# marbles_v70.net
KiCad netlist of a schematic drawn in EAGLE
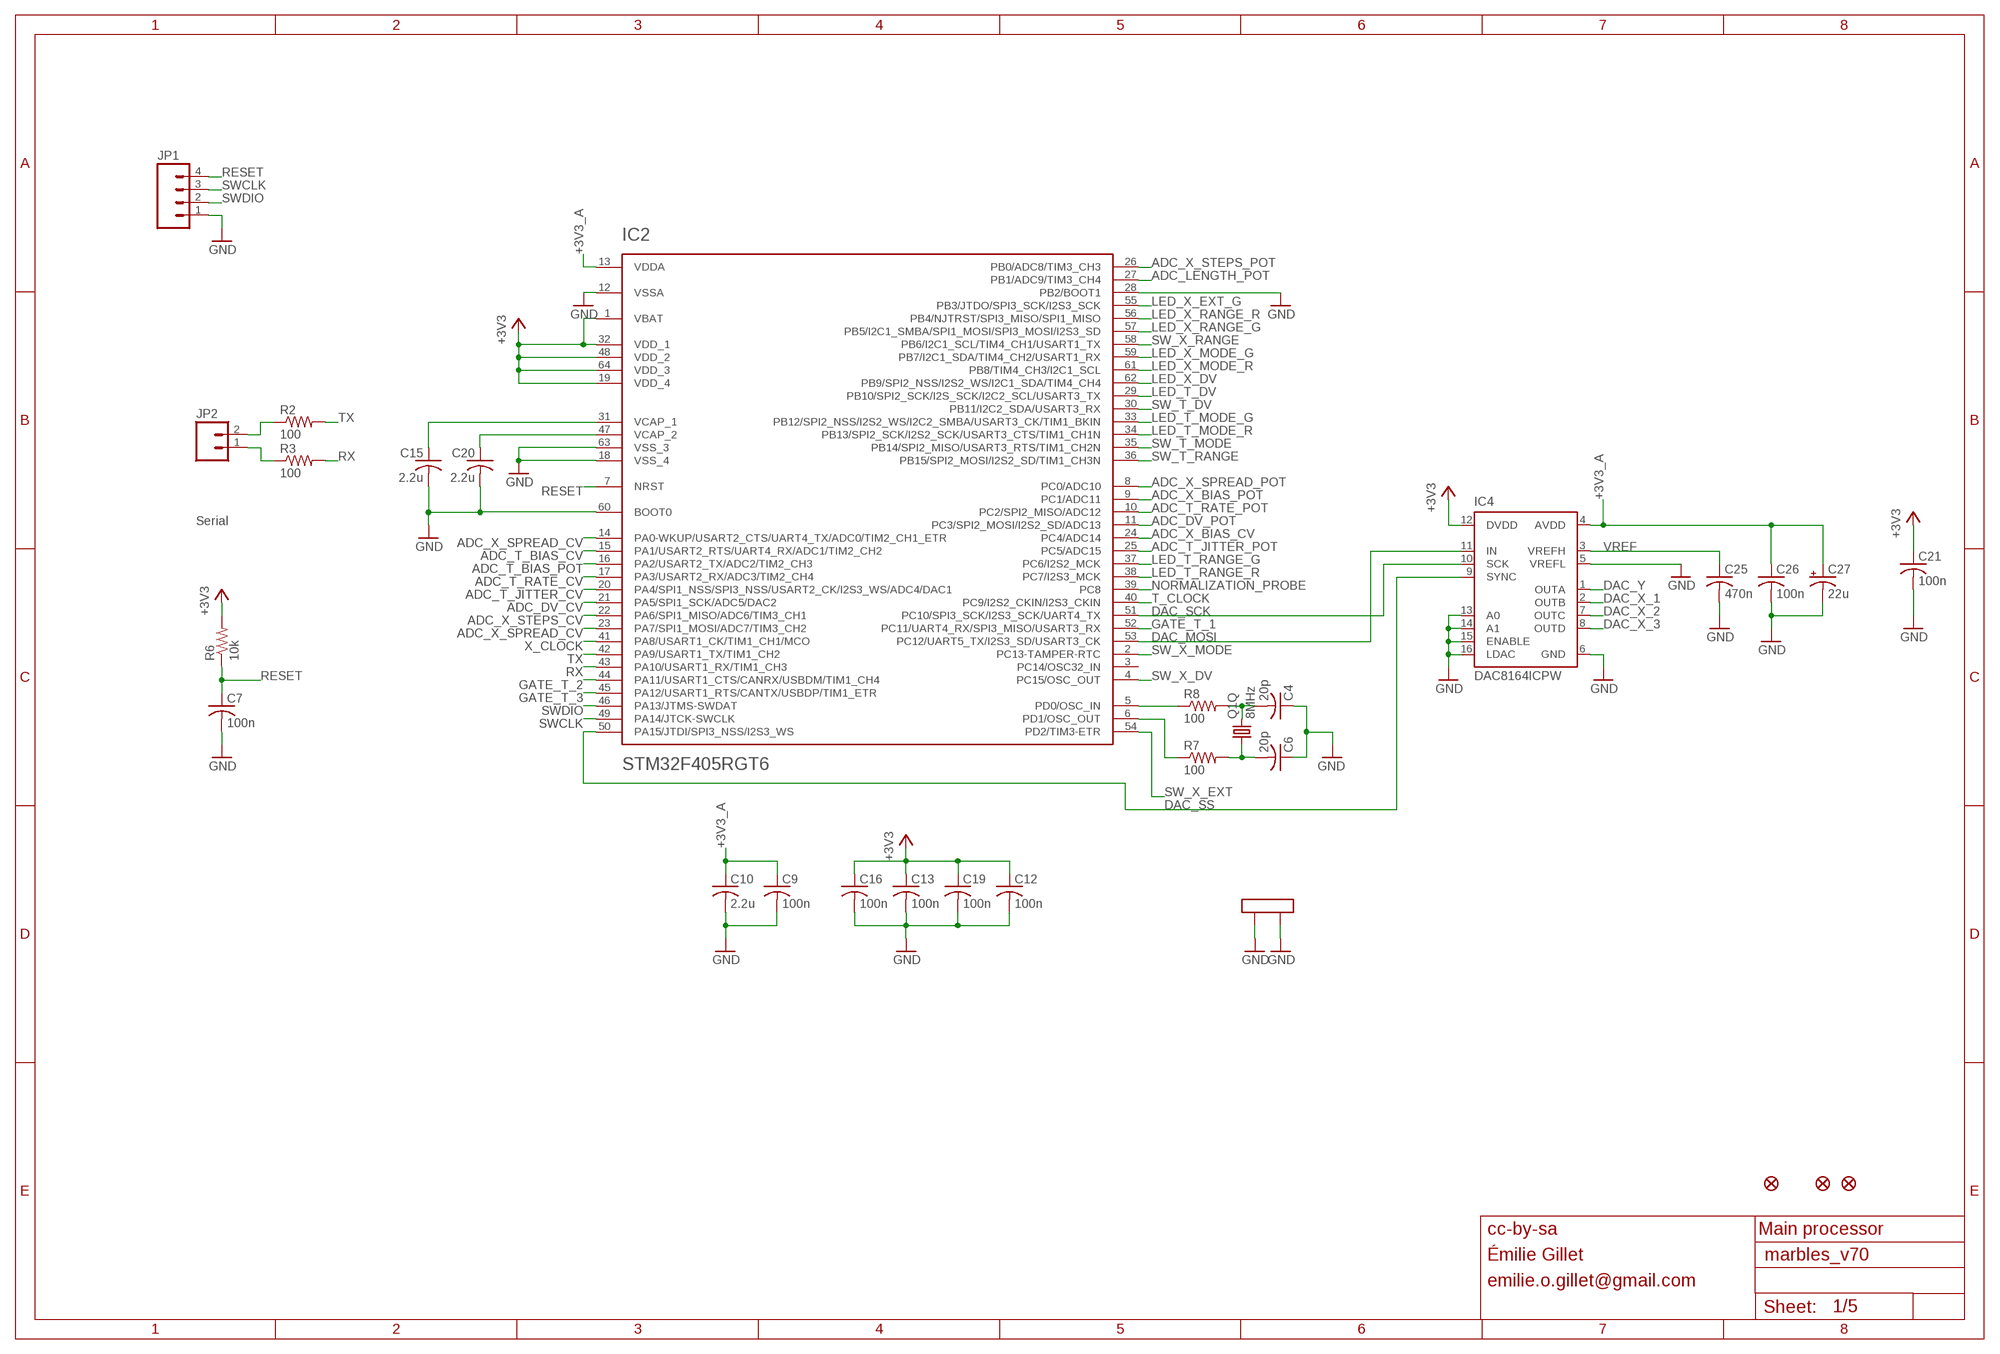
[diagram p0: schematic, sheet 1]
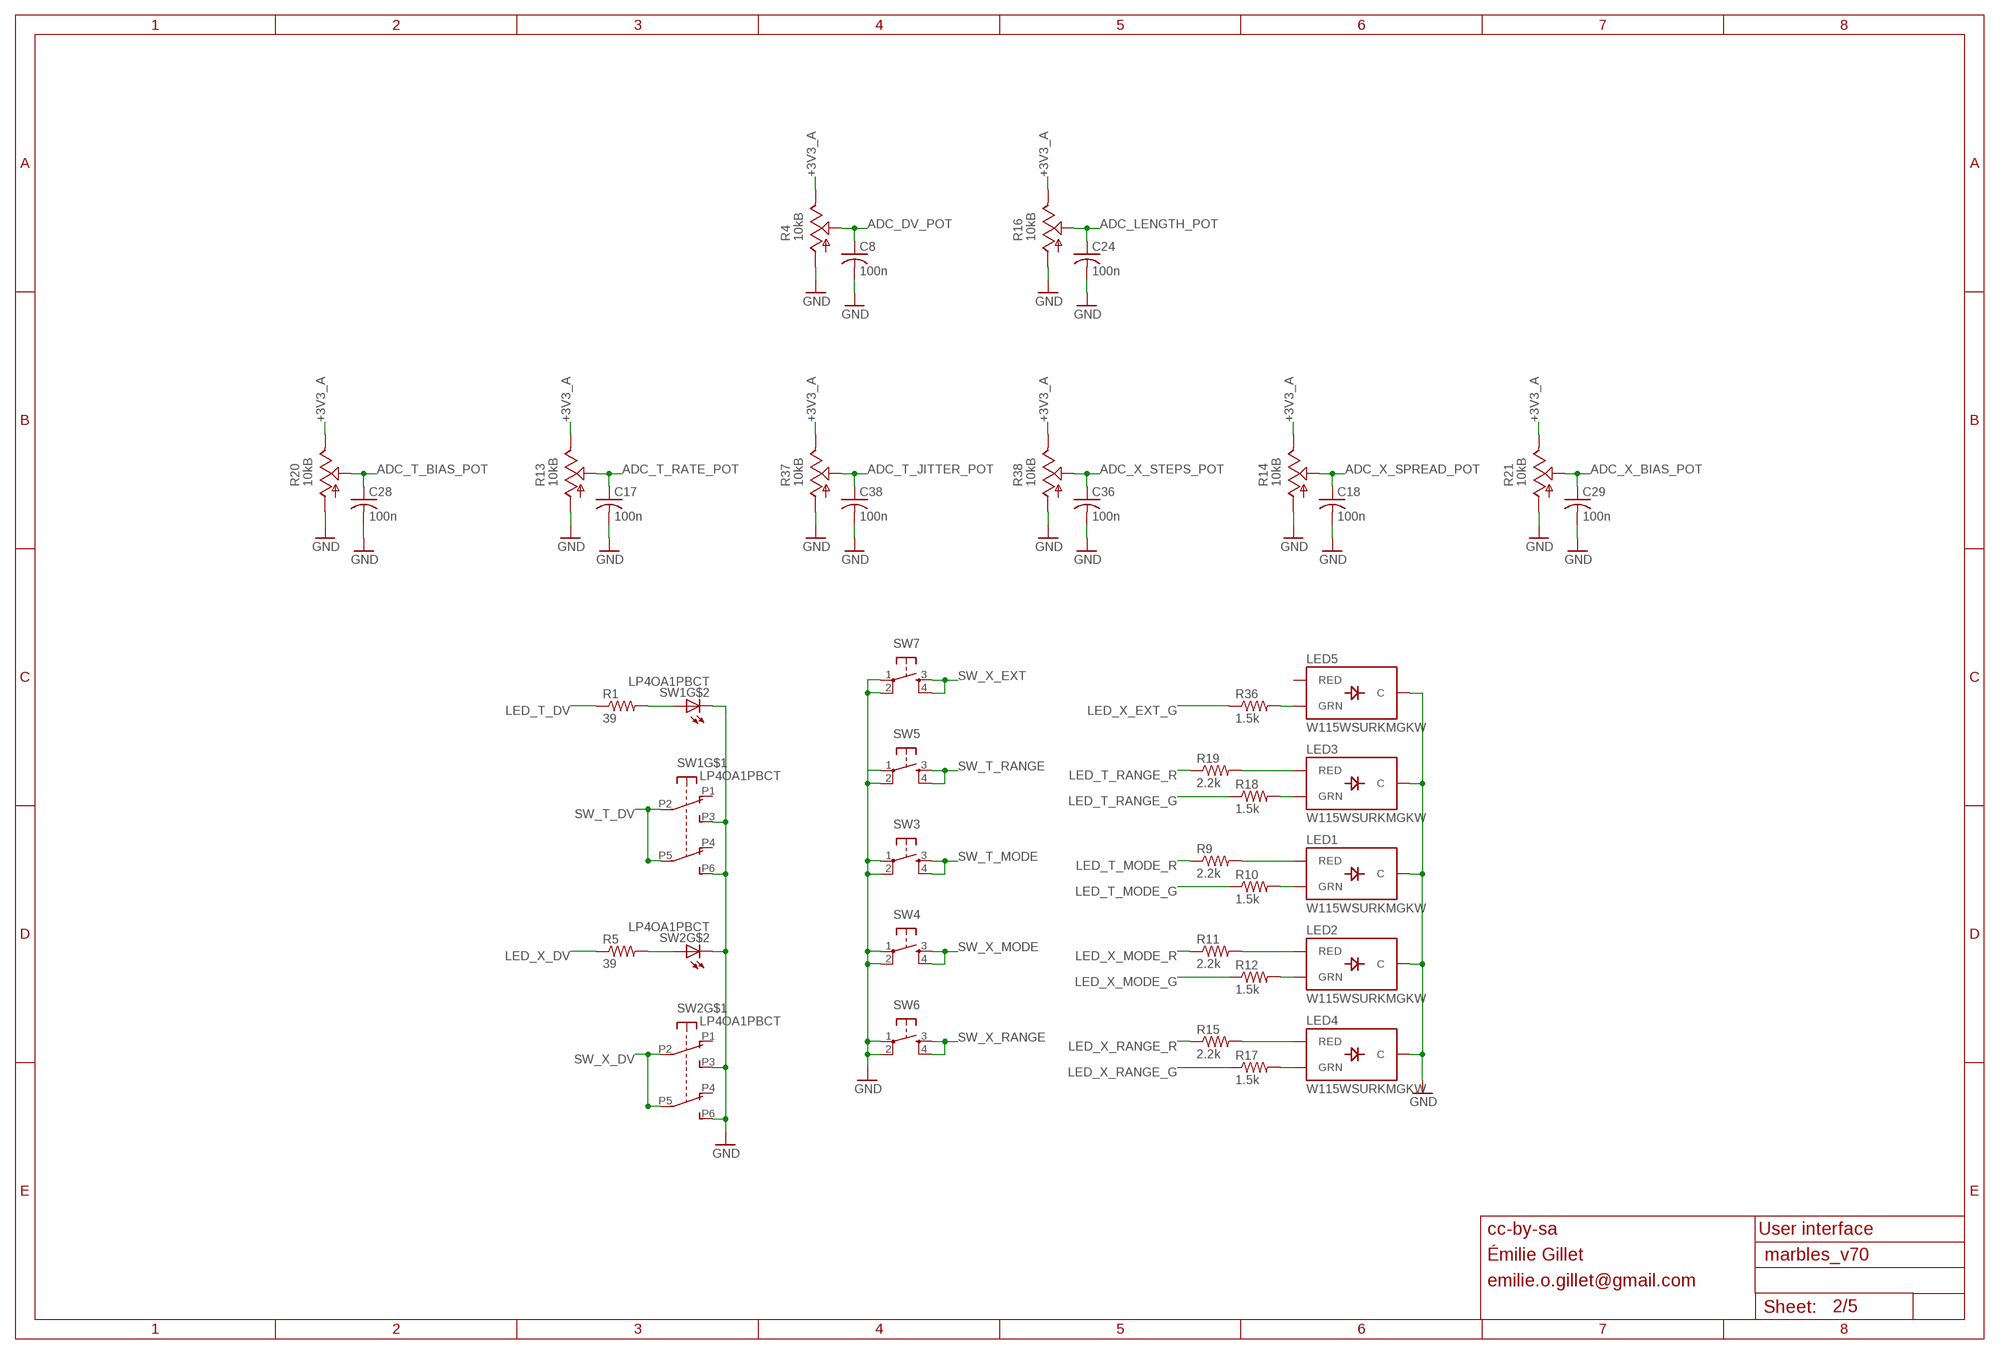
[diagram p1: schematic, sheet 2]
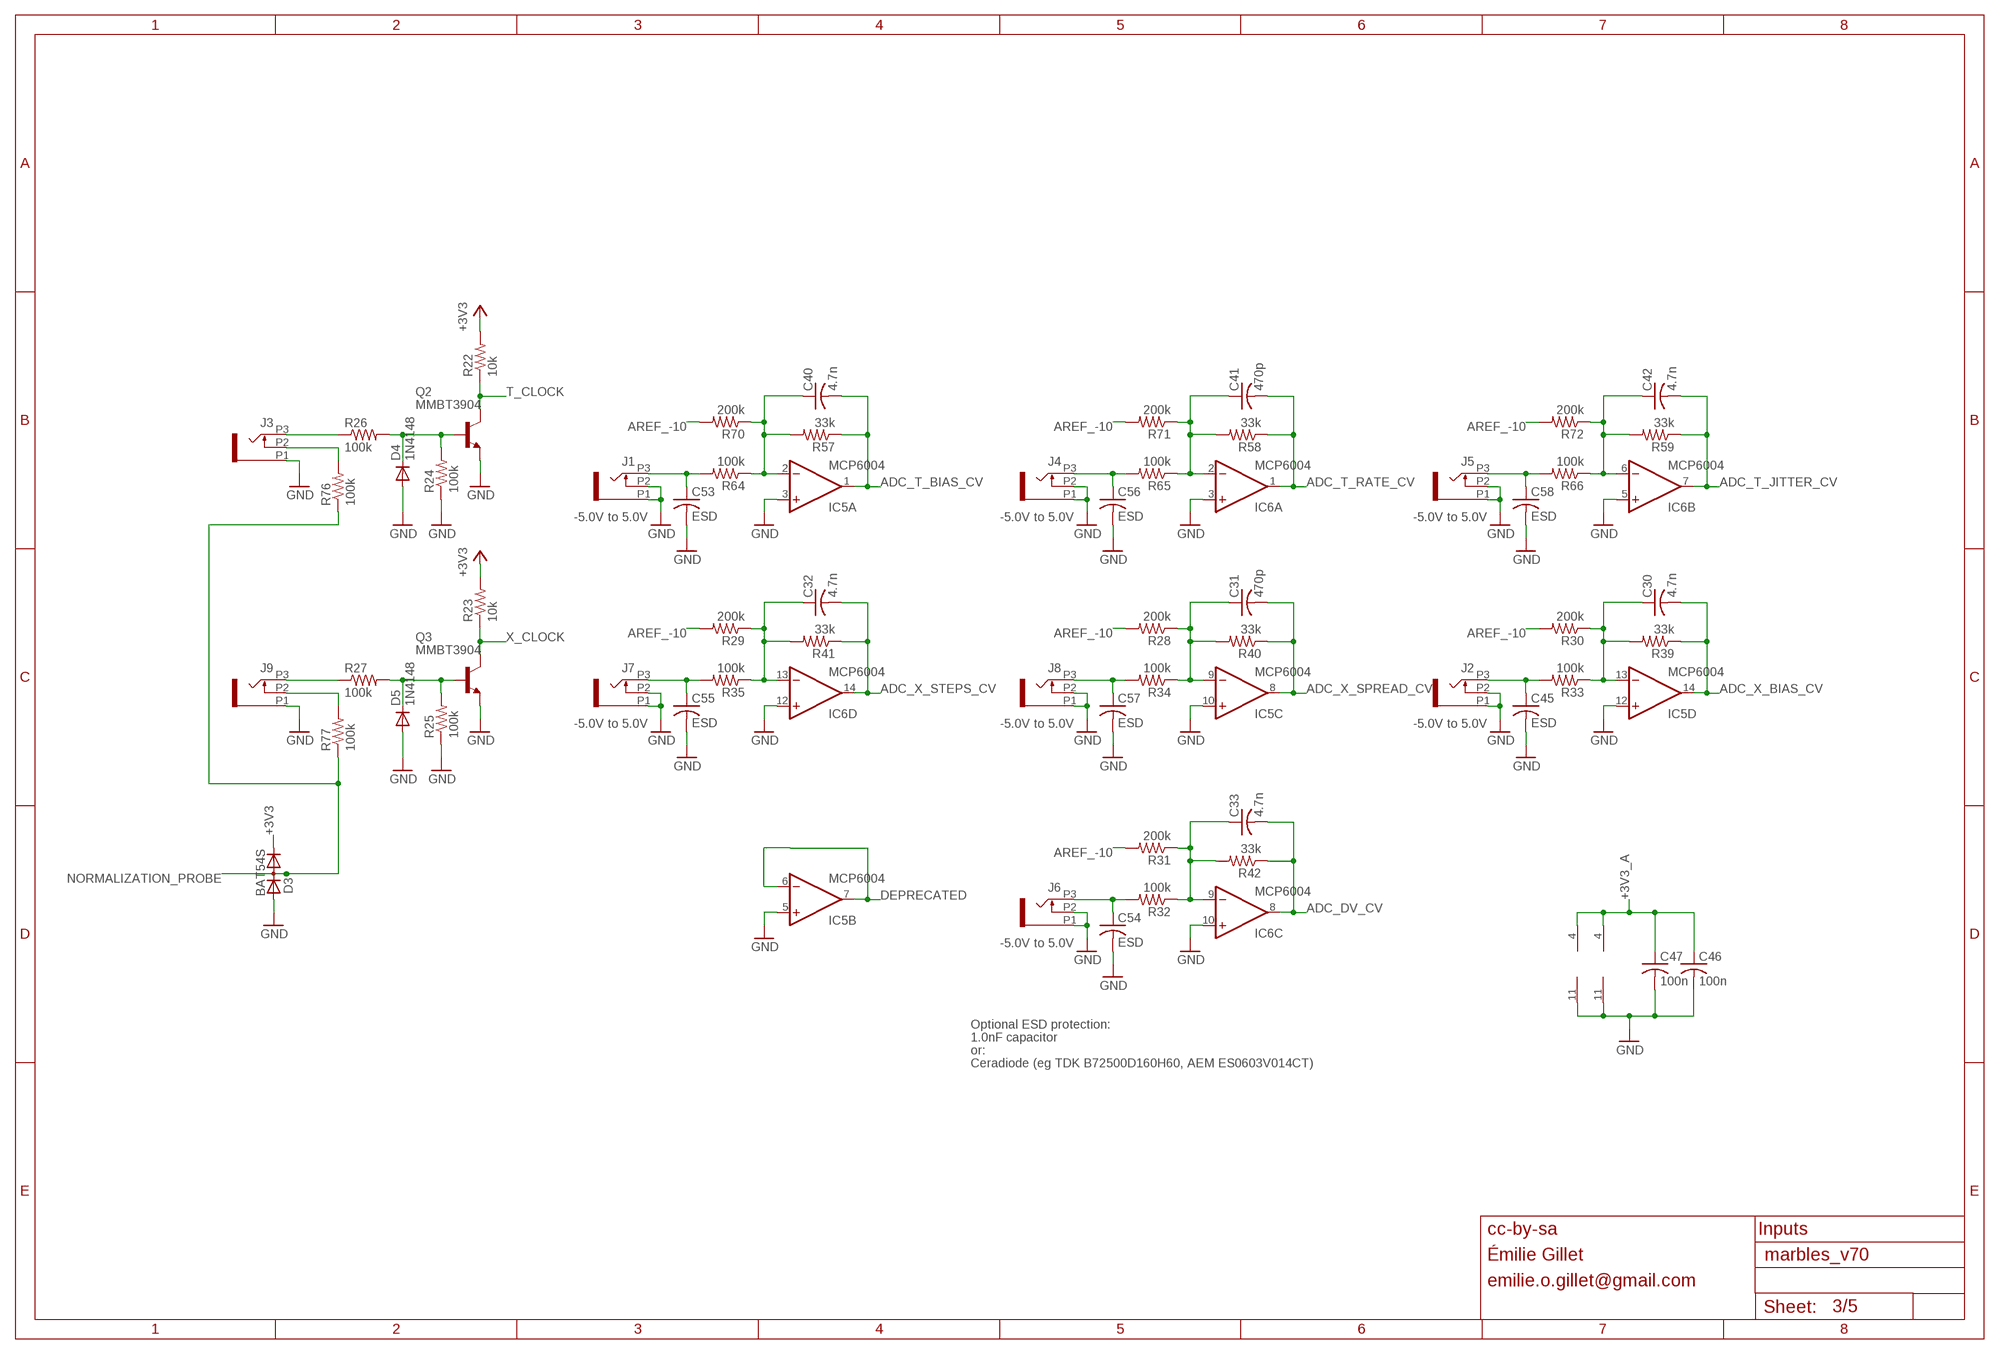
[diagram p2: schematic, sheet 3]
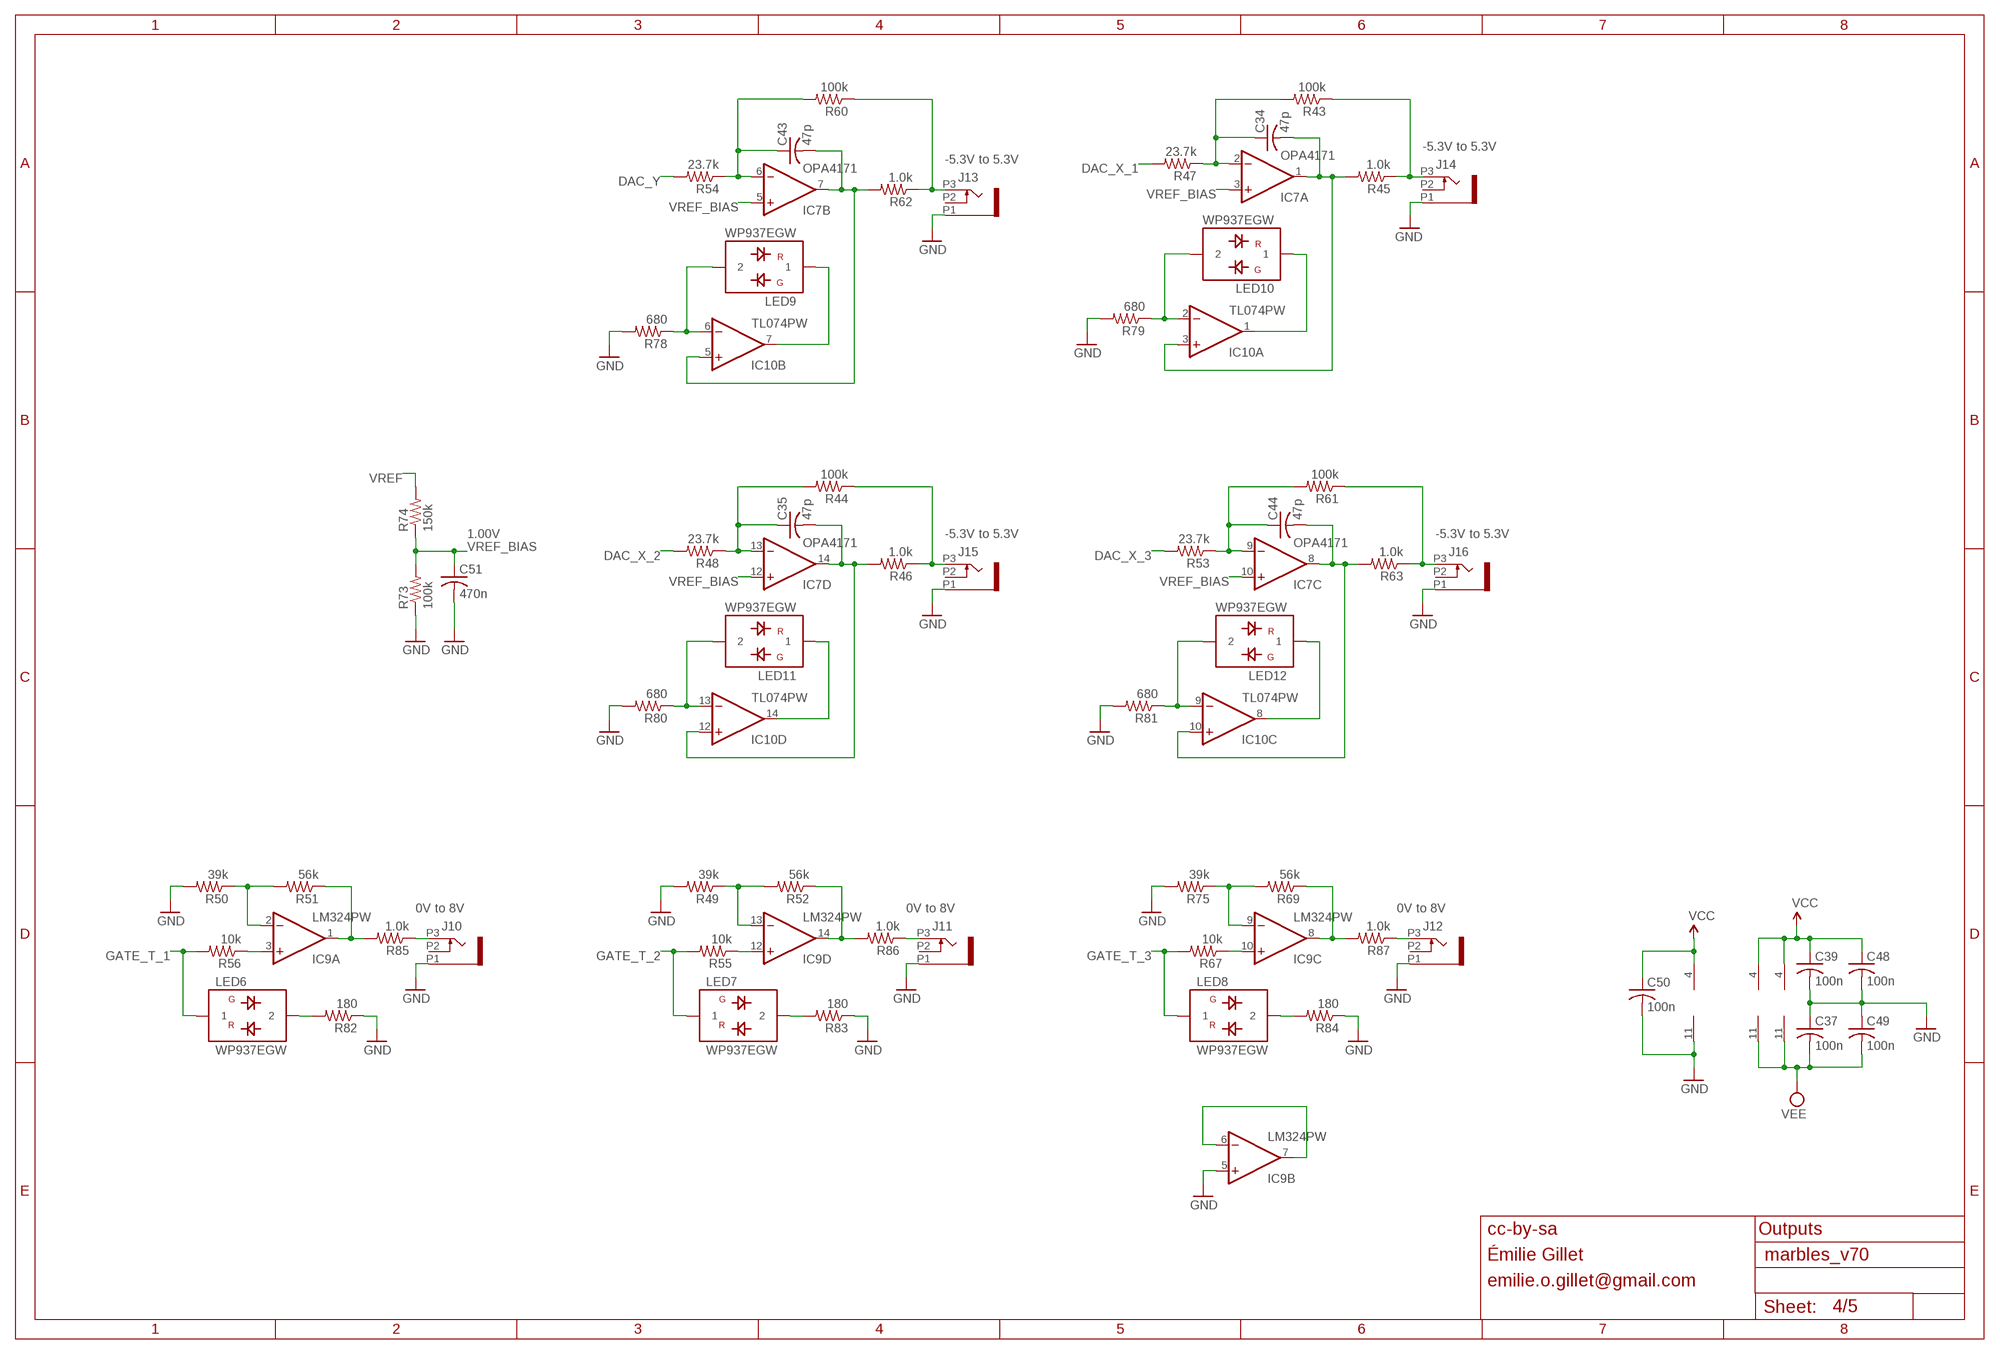
[diagram p3: schematic, sheet 4]
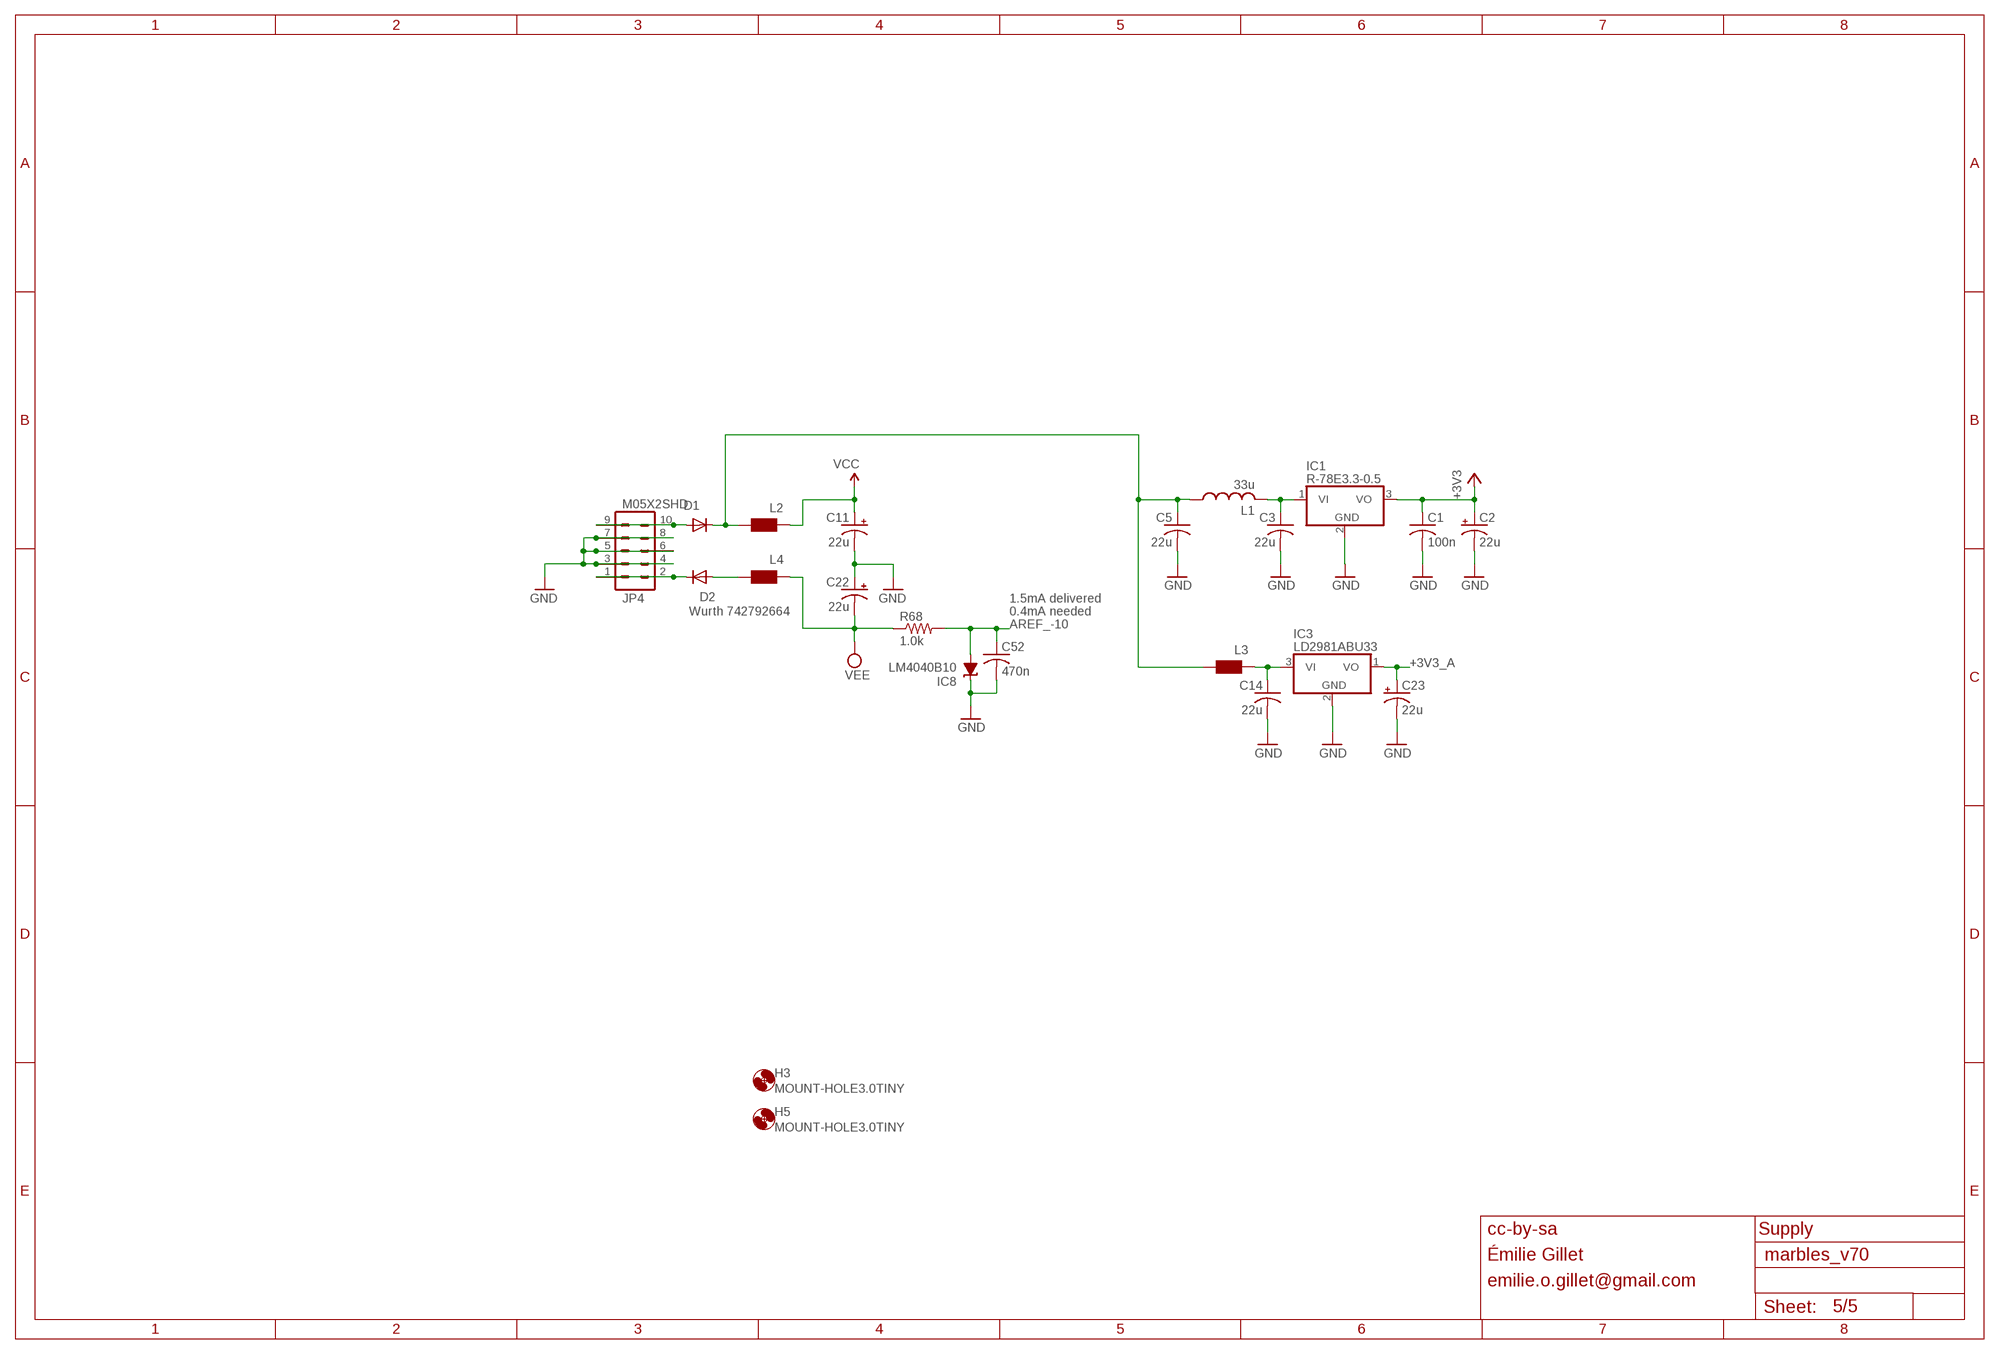
[diagram p4: schematic, sheet 5]

(export (version "E")
  (design (tool "Eeschema 10.0.6"))
  (components
    (comp (ref "C8")
      (value "100n")
      (footprint "eagle-import:C0402")
      (libsource (lib "eagle-import") (part "C-USC0402"))
    )
    (comp (ref "C17")
      (value "100n")
      (footprint "eagle-import:C0402")
      (libsource (lib "eagle-import") (part "C-USC0402"))
    )
    (comp (ref "C18")
      (value "100n")
      (footprint "eagle-import:C0402")
      (libsource (lib "eagle-import") (part "C-USC0402"))
    )
    (comp (ref "C24")
      (value "100n")
      (footprint "eagle-import:C0402")
      (libsource (lib "eagle-import") (part "C-USC0402"))
    )
    (comp (ref "C28")
      (value "100n")
      (footprint "eagle-import:C0402")
      (libsource (lib "eagle-import") (part "C-USC0402"))
    )
    (comp (ref "C29")
      (value "100n")
      (footprint "eagle-import:C0402")
      (libsource (lib "eagle-import") (part "C-USC0402"))
    )
    (comp (ref "C36")
      (value "100n")
      (footprint "eagle-import:C0402")
      (libsource (lib "eagle-import") (part "C-USC0402"))
    )
    (comp (ref "C38")
      (value "100n")
      (footprint "eagle-import:C0402")
      (libsource (lib "eagle-import") (part "C-USC0402"))
    )
    (comp (ref "LED1")
      (value "W115WSURKMGKW")
      (footprint "eagle-import:LED-BICOLOR-THROUGHHOLE-2.54")
      (libsource (lib "eagle-import") (part "LED-BICOLOR-THROUGHHOLE2.54"))
    )
    (comp (ref "LED2")
      (value "W115WSURKMGKW")
      (footprint "eagle-import:LED-BICOLOR-THROUGHHOLE-2.54")
      (libsource (lib "eagle-import") (part "LED-BICOLOR-THROUGHHOLE2.54"))
    )
    (comp (ref "LED3")
      (value "W115WSURKMGKW")
      (footprint "eagle-import:LED-BICOLOR-THROUGHHOLE-2.54")
      (libsource (lib "eagle-import") (part "LED-BICOLOR-THROUGHHOLE2.54"))
    )
    (comp (ref "LED4")
      (value "W115WSURKMGKW")
      (footprint "eagle-import:LED-BICOLOR-THROUGHHOLE-2.54")
      (libsource (lib "eagle-import") (part "LED-BICOLOR-THROUGHHOLE2.54"))
    )
    (comp (ref "LED5")
      (value "W115WSURKMGKW")
      (footprint "eagle-import:LED-BICOLOR-THROUGHHOLE-2.54")
      (libsource (lib "eagle-import") (part "LED-BICOLOR-THROUGHHOLE2.54"))
    )
    (comp (ref "R1")
      (value "39")
      (footprint "eagle-import:R0402")
      (libsource (lib "eagle-import") (part "R-US_R0402"))
    )
    (comp (ref "R4")
      (value "10kB")
      (footprint "eagle-import:ALPS_POT_VERTICAL_PS")
      (libsource (lib "eagle-import") (part "POT_USVERTICAL_PS"))
    )
    (comp (ref "R5")
      (value "39")
      (footprint "eagle-import:R0402")
      (libsource (lib "eagle-import") (part "R-US_R0402"))
    )
    (comp (ref "R9")
      (value "2.2k")
      (footprint "eagle-import:R0402")
      (libsource (lib "eagle-import") (part "R-US_R0402"))
    )
    (comp (ref "R10")
      (value "1.5k")
      (footprint "eagle-import:R0402")
      (libsource (lib "eagle-import") (part "R-US_R0402"))
    )
    (comp (ref "R11")
      (value "2.2k")
      (footprint "eagle-import:R0402")
      (libsource (lib "eagle-import") (part "R-US_R0402"))
    )
    (comp (ref "R12")
      (value "1.5k")
      (footprint "eagle-import:R0402")
      (libsource (lib "eagle-import") (part "R-US_R0402"))
    )
    (comp (ref "R13")
      (value "10kB")
      (footprint "eagle-import:ALPS_POT_VERTICAL_PS")
      (libsource (lib "eagle-import") (part "POT_USVERTICAL_PS"))
    )
    (comp (ref "R14")
      (value "10kB")
      (footprint "eagle-import:ALPS_POT_VERTICAL_PS")
      (libsource (lib "eagle-import") (part "POT_USVERTICAL_PS"))
    )
    (comp (ref "R15")
      (value "2.2k")
      (footprint "eagle-import:R0402")
      (libsource (lib "eagle-import") (part "R-US_R0402"))
    )
    (comp (ref "R16")
      (value "10kB")
      (footprint "eagle-import:ALPS_POT_VERTICAL_PS")
      (libsource (lib "eagle-import") (part "POT_USVERTICAL_PS"))
    )
    (comp (ref "R17")
      (value "1.5k")
      (footprint "eagle-import:R0402")
      (libsource (lib "eagle-import") (part "R-US_R0402"))
    )
    (comp (ref "R18")
      (value "1.5k")
      (footprint "eagle-import:R0402")
      (libsource (lib "eagle-import") (part "R-US_R0402"))
    )
    (comp (ref "R19")
      (value "2.2k")
      (footprint "eagle-import:R0402")
      (libsource (lib "eagle-import") (part "R-US_R0402"))
    )
    (comp (ref "R20")
      (value "10kB")
      (footprint "eagle-import:ALPS_POT_VERTICAL_PS")
      (libsource (lib "eagle-import") (part "POT_USVERTICAL_PS"))
    )
    (comp (ref "R21")
      (value "10kB")
      (footprint "eagle-import:ALPS_POT_VERTICAL_PS")
      (libsource (lib "eagle-import") (part "POT_USVERTICAL_PS"))
    )
    (comp (ref "R36")
      (value "1.5k")
      (footprint "eagle-import:R0402")
      (libsource (lib "eagle-import") (part "R-US_R0402"))
    )
    (comp (ref "R37")
      (value "10kB")
      (footprint "eagle-import:ALPS_POT_VERTICAL_PS")
      (libsource (lib "eagle-import") (part "POT_USVERTICAL_PS"))
    )
    (comp (ref "R38")
      (value "10kB")
      (footprint "eagle-import:ALPS_POT_VERTICAL_PS")
      (libsource (lib "eagle-import") (part "POT_USVERTICAL_PS"))
    )
    (comp (ref "SW1")
      (value "LP4OA1PBCT")
      (footprint "eagle-import:LP4OA1PBCT")
      (libsource (lib "eagle-import") (part "LP4OA1PBCT"))
    )
    (comp (ref "SW2")
      (value "LP4OA1PBCT")
      (footprint "eagle-import:LP4OA1PBCT")
      (libsource (lib "eagle-import") (part "LP4OA1PBCT"))
    )
    (comp (ref "SW3")
      (value "TAC_SWITCHPTH")
      (footprint "eagle-import:TACTILE-PTH")
      (libsource (lib "eagle-import") (part "TAC_SWITCHPTH"))
    )
    (comp (ref "SW4")
      (value "TAC_SWITCHPTH")
      (footprint "eagle-import:TACTILE-PTH")
      (libsource (lib "eagle-import") (part "TAC_SWITCHPTH"))
    )
    (comp (ref "SW5")
      (value "TAC_SWITCHPTH")
      (footprint "eagle-import:TACTILE-PTH")
      (libsource (lib "eagle-import") (part "TAC_SWITCHPTH"))
    )
    (comp (ref "SW6")
      (value "TAC_SWITCHPTH")
      (footprint "eagle-import:TACTILE-PTH")
      (libsource (lib "eagle-import") (part "TAC_SWITCHPTH"))
    )
    (comp (ref "SW7")
      (value "TAC_SWITCHPTH")
      (footprint "eagle-import:TACTILE-PTH")
      (libsource (lib "eagle-import") (part "TAC_SWITCHPTH"))
    )
    (comp (ref "C4")
      (value "20p")
      (footprint "eagle-import:C0402")
      (libsource (lib "eagle-import") (part "C-USC0402"))
    )
    (comp (ref "C6")
      (value "20p")
      (footprint "eagle-import:C0402")
      (libsource (lib "eagle-import") (part "C-USC0402"))
    )
    (comp (ref "C7")
      (value "100n")
      (footprint "eagle-import:C0402")
      (libsource (lib "eagle-import") (part "C-USC0402"))
    )
    (comp (ref "C9")
      (value "100n")
      (footprint "eagle-import:C0402")
      (libsource (lib "eagle-import") (part "C-USC0402"))
    )
    (comp (ref "C10")
      (value "2.2u")
      (footprint "eagle-import:C0805")
      (libsource (lib "eagle-import") (part "C-USC0805"))
    )
    (comp (ref "C12")
      (value "100n")
      (footprint "eagle-import:C0402")
      (libsource (lib "eagle-import") (part "C-USC0402"))
    )
    (comp (ref "C13")
      (value "100n")
      (footprint "eagle-import:C0402")
      (libsource (lib "eagle-import") (part "C-USC0402"))
    )
    (comp (ref "C15")
      (value "2.2u")
      (footprint "eagle-import:C0805")
      (libsource (lib "eagle-import") (part "C-USC0805"))
    )
    (comp (ref "C16")
      (value "100n")
      (footprint "eagle-import:C0402")
      (libsource (lib "eagle-import") (part "C-USC0402"))
    )
    (comp (ref "C19")
      (value "100n")
      (footprint "eagle-import:C0402")
      (libsource (lib "eagle-import") (part "C-USC0402"))
    )
    (comp (ref "C20")
      (value "2.2u")
      (footprint "eagle-import:C0805")
      (libsource (lib "eagle-import") (part "C-USC0805"))
    )
    (comp (ref "C21")
      (value "100n")
      (footprint "eagle-import:C0402")
      (libsource (lib "eagle-import") (part "C-USC0402"))
    )
    (comp (ref "C25")
      (value "470n")
      (footprint "eagle-import:C0402")
      (libsource (lib "eagle-import") (part "C-USC0402"))
    )
    (comp (ref "C26")
      (value "100n")
      (footprint "eagle-import:C0402")
      (libsource (lib "eagle-import") (part "C-USC0402"))
    )
    (comp (ref "C27")
      (value "22u")
      (footprint "eagle-import:PANASONIC_C")
      (libsource (lib "eagle-import") (part "CPOL-USC"))
    )
    (comp (ref "F1")
      (value "FIDUCIAL1X2")
      (footprint "eagle-import:FIDUCIAL-1X2")
      (libsource (lib "eagle-import") (part "FIDUCIAL1X2"))
    )
    (comp (ref "F2")
      (value "FIDUCIAL1X2")
      (footprint "eagle-import:FIDUCIAL-1X2")
      (libsource (lib "eagle-import") (part "FIDUCIAL1X2"))
    )
    (comp (ref "F3")
      (value "FIDUCIAL1X2")
      (footprint "eagle-import:FIDUCIAL-1X2")
      (libsource (lib "eagle-import") (part "FIDUCIAL1X2"))
    )
    (comp (ref "IC2")
      (value "STM32F405RGT6")
      (footprint "eagle-import:TQFP-10X10-64")
      (libsource (lib "eagle-import") (part "STM32F20X"))
    )
    (comp (ref "IC4")
      (value "DAC8164ICPW")
      (footprint "eagle-import:SOP65P640X110-16N")
      (libsource (lib "eagle-import") (part "DAC8564"))
    )
    (comp (ref "JP1")
      (value "M04PTH")
      (footprint "eagle-import:1X04")
      (libsource (lib "eagle-import") (part "M04PTH"))
    )
    (comp (ref "JP2")
      (value "M02PTH")
      (footprint "eagle-import:1X02")
      (libsource (lib "eagle-import") (part "M02PTH"))
    )
    (comp (ref "Q1")
      (value "8MHz")
      (footprint "eagle-import:CTS406")
      (libsource (lib "eagle-import") (part "CRYSTAL"))
    )
    (comp (ref "R2")
      (value "100")
      (footprint "eagle-import:R0402")
      (libsource (lib "eagle-import") (part "R-US_R0402"))
    )
    (comp (ref "R3")
      (value "100")
      (footprint "eagle-import:R0402")
      (libsource (lib "eagle-import") (part "R-US_R0402"))
    )
    (comp (ref "R6")
      (value "10k")
      (footprint "eagle-import:R0402")
      (libsource (lib "eagle-import") (part "R-US_R0402"))
    )
    (comp (ref "R7")
      (value "100")
      (footprint "eagle-import:R0402")
      (libsource (lib "eagle-import") (part "R-US_R0402"))
    )
    (comp (ref "R8")
      (value "100")
      (footprint "eagle-import:R0402")
      (libsource (lib "eagle-import") (part "R-US_R0402"))
    )
    (comp (ref "C1")
      (value "100n")
      (footprint "eagle-import:C0402")
      (libsource (lib "eagle-import") (part "C-USC0402"))
    )
    (comp (ref "C2")
      (value "22u")
      (footprint "eagle-import:PANASONIC_C")
      (libsource (lib "eagle-import") (part "CPOL-USC"))
    )
    (comp (ref "C3")
      (value "22u")
      (footprint "eagle-import:C1206")
      (libsource (lib "eagle-import") (part "C-USC1206"))
    )
    (comp (ref "C5")
      (value "22u")
      (footprint "eagle-import:C1206")
      (libsource (lib "eagle-import") (part "C-USC1206"))
    )
    (comp (ref "C11")
      (value "22u")
      (footprint "eagle-import:PANASONIC_C")
      (libsource (lib "eagle-import") (part "CPOL-USC"))
    )
    (comp (ref "C14")
      (value "22u")
      (footprint "eagle-import:C1206")
      (libsource (lib "eagle-import") (part "C-USC1206"))
    )
    (comp (ref "C22")
      (value "22u")
      (footprint "eagle-import:PANASONIC_C")
      (libsource (lib "eagle-import") (part "CPOL-USC"))
    )
    (comp (ref "C23")
      (value "22u")
      (footprint "eagle-import:PANASONIC_C")
      (libsource (lib "eagle-import") (part "CPOL-USC"))
    )
    (comp (ref "C52")
      (value "470n")
      (footprint "eagle-import:C0402")
      (libsource (lib "eagle-import") (part "C-USC0402"))
    )
    (comp (ref "D1")
      (value "1N5819HW")
      (footprint "eagle-import:SOD123")
      (libsource (lib "eagle-import") (part "DIODE-SOD123"))
    )
    (comp (ref "D2")
      (value "1N5819HW")
      (footprint "eagle-import:SOD123")
      (libsource (lib "eagle-import") (part "DIODE-SOD123"))
    )
    (comp (ref "H3")
      (value "MOUNT-HOLE3.0TINY")
      (footprint "eagle-import:3,0TINY")
      (libsource (lib "eagle-import") (part "MOUNT-HOLE3.0TINY"))
    )
    (comp (ref "H5")
      (value "MOUNT-HOLE3.0TINY")
      (footprint "eagle-import:3,0TINY")
      (libsource (lib "eagle-import") (part "MOUNT-HOLE3.0TINY"))
    )
    (comp (ref "IC1")
      (value "R-78E3.3-0.5")
      (footprint "eagle-import:WE78")
      (libsource (lib "eagle-import") (part "WE173950378"))
    )
    (comp (ref "IC3")
      (value "LD2981ABU33")
      (footprint "eagle-import:SOT89")
      (libsource (lib "eagle-import") (part "LD2981ABU"))
    )
    (comp (ref "IC8")
      (value "LM4040B10")
      (footprint "eagle-import:DBZ_R-PDSO-G3")
      (libsource (lib "eagle-import") (part "LM4041DBZB12"))
    )
    (comp (ref "JP4")
      (value "M05X2SHD")
      (footprint "eagle-import:2X5-SHROUDED")
      (libsource (lib "eagle-import") (part "M05X2SHD"))
    )
    (comp (ref "L1")
      (value "33u")
      (footprint "eagle-import:L2012C")
      (libsource (lib "eagle-import") (part "L-USL2012C"))
    )
    (comp (ref "L2")
      (value "WE-CBF_0603")
      (footprint "eagle-import:0603")
      (libsource (lib "eagle-import") (part "WE-CBF_0603"))
    )
    (comp (ref "L3")
      (value "WE-CBF_0603")
      (footprint "eagle-import:0603")
      (libsource (lib "eagle-import") (part "WE-CBF_0603"))
    )
    (comp (ref "L4")
      (value "WE-CBF_0603")
      (footprint "eagle-import:0603")
      (libsource (lib "eagle-import") (part "WE-CBF_0603"))
    )
    (comp (ref "R68")
      (value "1.0k")
      (footprint "eagle-import:R0402")
      (libsource (lib "eagle-import") (part "R-US_R0402"))
    )
    (comp (ref "C30")
      (value "4.7n")
      (footprint "eagle-import:C0402")
      (libsource (lib "eagle-import") (part "C-USC0402"))
    )
    (comp (ref "C31")
      (value "470p")
      (footprint "eagle-import:C0402")
      (libsource (lib "eagle-import") (part "C-USC0402"))
    )
    (comp (ref "C32")
      (value "4.7n")
      (footprint "eagle-import:C0402")
      (libsource (lib "eagle-import") (part "C-USC0402"))
    )
    (comp (ref "C33")
      (value "4.7n")
      (footprint "eagle-import:C0402")
      (libsource (lib "eagle-import") (part "C-USC0402"))
    )
    (comp (ref "C40")
      (value "4.7n")
      (footprint "eagle-import:C0402")
      (libsource (lib "eagle-import") (part "C-USC0402"))
    )
    (comp (ref "C41")
      (value "470p")
      (footprint "eagle-import:C0402")
      (libsource (lib "eagle-import") (part "C-USC0402"))
    )
    (comp (ref "C42")
      (value "4.7n")
      (footprint "eagle-import:C0402")
      (libsource (lib "eagle-import") (part "C-USC0402"))
    )
    (comp (ref "C45")
      (value "ESD")
      (footprint "eagle-import:C0603")
      (libsource (lib "eagle-import") (part "C-USC0603"))
    )
    (comp (ref "C46")
      (value "100n")
      (footprint "eagle-import:C0402")
      (libsource (lib "eagle-import") (part "C-USC0402"))
    )
    (comp (ref "C47")
      (value "100n")
      (footprint "eagle-import:C0402")
      (libsource (lib "eagle-import") (part "C-USC0402"))
    )
    (comp (ref "C53")
      (value "ESD")
      (footprint "eagle-import:C0603")
      (libsource (lib "eagle-import") (part "C-USC0603"))
    )
    (comp (ref "C54")
      (value "ESD")
      (footprint "eagle-import:C0603")
      (libsource (lib "eagle-import") (part "C-USC0603"))
    )
    (comp (ref "C55")
      (value "ESD")
      (footprint "eagle-import:C0603")
      (libsource (lib "eagle-import") (part "C-USC0603"))
    )
    (comp (ref "C56")
      (value "ESD")
      (footprint "eagle-import:C0603")
      (libsource (lib "eagle-import") (part "C-USC0603"))
    )
    (comp (ref "C57")
      (value "ESD")
      (footprint "eagle-import:C0603")
      (libsource (lib "eagle-import") (part "C-USC0603"))
    )
    (comp (ref "C58")
      (value "ESD")
      (footprint "eagle-import:C0603")
      (libsource (lib "eagle-import") (part "C-USC0603"))
    )
    (comp (ref "D3")
      (value "BAT54S")
      (footprint "eagle-import:SOT23")
      (libsource (lib "eagle-import") (part "DIODE_2CACA-SOT23"))
    )
    (comp (ref "D4")
      (value "1N4148")
      (footprint "eagle-import:SOD523")
      (libsource (lib "eagle-import") (part "DIODE-SOD523"))
    )
    (comp (ref "D5")
      (value "1N4148")
      (footprint "eagle-import:SOD523")
      (libsource (lib "eagle-import") (part "DIODE-SOD523"))
    )
    (comp (ref "IC5")
      (value "MCP6004")
      (footprint "eagle-import:TSSOP14_065")
      (libsource (lib "eagle-import") (part "TL074PW"))
    )
    (comp (ref "IC6")
      (value "MCP6004")
      (footprint "eagle-import:TSSOP14_065")
      (libsource (lib "eagle-import") (part "TL074PW"))
    )
    (comp (ref "J1")
      (value "PJ301_THONKICONN6")
      (footprint "eagle-import:WQP_PJ_301M6")
      (libsource (lib "eagle-import") (part "PJ301_THONKICONN6"))
    )
    (comp (ref "J2")
      (value "PJ301_THONKICONN6")
      (footprint "eagle-import:WQP_PJ_301M6")
      (libsource (lib "eagle-import") (part "PJ301_THONKICONN6"))
    )
    (comp (ref "J3")
      (value "PJ301_THONKICONN6")
      (footprint "eagle-import:WQP_PJ_301M6")
      (libsource (lib "eagle-import") (part "PJ301_THONKICONN6"))
    )
    (comp (ref "J4")
      (value "PJ301_THONKICONN6")
      (footprint "eagle-import:WQP_PJ_301M6")
      (libsource (lib "eagle-import") (part "PJ301_THONKICONN6"))
    )
    (comp (ref "J5")
      (value "PJ301_THONKICONN6")
      (footprint "eagle-import:WQP_PJ_301M6")
      (libsource (lib "eagle-import") (part "PJ301_THONKICONN6"))
    )
    (comp (ref "J6")
      (value "PJ301_THONKICONN6")
      (footprint "eagle-import:WQP_PJ_301M6")
      (libsource (lib "eagle-import") (part "PJ301_THONKICONN6"))
    )
    (comp (ref "J7")
      (value "PJ301_THONKICONN6")
      (footprint "eagle-import:WQP_PJ_301M6")
      (libsource (lib "eagle-import") (part "PJ301_THONKICONN6"))
    )
    (comp (ref "J8")
      (value "PJ301_THONKICONN6")
      (footprint "eagle-import:WQP_PJ_301M6")
      (libsource (lib "eagle-import") (part "PJ301_THONKICONN6"))
    )
    (comp (ref "J9")
      (value "PJ301_THONKICONN6")
      (footprint "eagle-import:WQP_PJ_301M6")
      (libsource (lib "eagle-import") (part "PJ301_THONKICONN6"))
    )
    (comp (ref "Q2")
      (value "MMBT3904")
      (footprint "eagle-import:SOT23-BEC")
      (libsource (lib "eagle-import") (part "-NPN-SOT23-BECMMBT3904LT1"))
    )
    (comp (ref "Q3")
      (value "MMBT3904")
      (footprint "eagle-import:SOT23-BEC")
      (libsource (lib "eagle-import") (part "-NPN-SOT23-BECMMBT3904LT1"))
    )
    (comp (ref "R22")
      (value "10k")
      (footprint "eagle-import:R0402")
      (libsource (lib "eagle-import") (part "R-US_R0402"))
    )
    (comp (ref "R23")
      (value "10k")
      (footprint "eagle-import:R0402")
      (libsource (lib "eagle-import") (part "R-US_R0402"))
    )
    (comp (ref "R24")
      (value "100k")
      (footprint "eagle-import:R0402")
      (libsource (lib "eagle-import") (part "R-US_R0402"))
    )
    (comp (ref "R25")
      (value "100k")
      (footprint "eagle-import:R0402")
      (libsource (lib "eagle-import") (part "R-US_R0402"))
    )
    (comp (ref "R26")
      (value "100k")
      (footprint "eagle-import:R0402")
      (libsource (lib "eagle-import") (part "R-US_R0402"))
    )
    (comp (ref "R27")
      (value "100k")
      (footprint "eagle-import:R0402")
      (libsource (lib "eagle-import") (part "R-US_R0402"))
    )
    (comp (ref "R28")
      (value "200k")
      (footprint "eagle-import:R0402")
      (libsource (lib "eagle-import") (part "R-US_R0402"))
    )
    (comp (ref "R29")
      (value "200k")
      (footprint "eagle-import:R0402")
      (libsource (lib "eagle-import") (part "R-US_R0402"))
    )
    (comp (ref "R30")
      (value "200k")
      (footprint "eagle-import:R0402")
      (libsource (lib "eagle-import") (part "R-US_R0402"))
    )
    (comp (ref "R31")
      (value "200k")
      (footprint "eagle-import:R0402")
      (libsource (lib "eagle-import") (part "R-US_R0402"))
    )
    (comp (ref "R32")
      (value "100k")
      (footprint "eagle-import:R0402")
      (libsource (lib "eagle-import") (part "R-US_R0402"))
    )
    (comp (ref "R33")
      (value "100k")
      (footprint "eagle-import:R0402")
      (libsource (lib "eagle-import") (part "R-US_R0402"))
    )
    (comp (ref "R34")
      (value "100k")
      (footprint "eagle-import:R0402")
      (libsource (lib "eagle-import") (part "R-US_R0402"))
    )
    (comp (ref "R35")
      (value "100k")
      (footprint "eagle-import:R0402")
      (libsource (lib "eagle-import") (part "R-US_R0402"))
    )
    (comp (ref "R39")
      (value "33k")
      (footprint "eagle-import:R0402")
      (libsource (lib "eagle-import") (part "R-US_R0402"))
    )
    (comp (ref "R40")
      (value "33k")
      (footprint "eagle-import:R0402")
      (libsource (lib "eagle-import") (part "R-US_R0402"))
    )
    (comp (ref "R41")
      (value "33k")
      (footprint "eagle-import:R0402")
      (libsource (lib "eagle-import") (part "R-US_R0402"))
    )
    (comp (ref "R42")
      (value "33k")
      (footprint "eagle-import:R0402")
      (libsource (lib "eagle-import") (part "R-US_R0402"))
    )
    (comp (ref "R57")
      (value "33k")
      (footprint "eagle-import:R0402")
      (libsource (lib "eagle-import") (part "R-US_R0402"))
    )
    (comp (ref "R58")
      (value "33k")
      (footprint "eagle-import:R0402")
      (libsource (lib "eagle-import") (part "R-US_R0402"))
    )
    (comp (ref "R59")
      (value "33k")
      (footprint "eagle-import:R0402")
      (libsource (lib "eagle-import") (part "R-US_R0402"))
    )
    (comp (ref "R64")
      (value "100k")
      (footprint "eagle-import:R0402")
      (libsource (lib "eagle-import") (part "R-US_R0402"))
    )
    (comp (ref "R65")
      (value "100k")
      (footprint "eagle-import:R0402")
      (libsource (lib "eagle-import") (part "R-US_R0402"))
    )
    (comp (ref "R66")
      (value "100k")
      (footprint "eagle-import:R0402")
      (libsource (lib "eagle-import") (part "R-US_R0402"))
    )
    (comp (ref "R70")
      (value "200k")
      (footprint "eagle-import:R0402")
      (libsource (lib "eagle-import") (part "R-US_R0402"))
    )
    (comp (ref "R71")
      (value "200k")
      (footprint "eagle-import:R0402")
      (libsource (lib "eagle-import") (part "R-US_R0402"))
    )
    (comp (ref "R72")
      (value "200k")
      (footprint "eagle-import:R0402")
      (libsource (lib "eagle-import") (part "R-US_R0402"))
    )
    (comp (ref "R76")
      (value "100k")
      (footprint "eagle-import:R0402")
      (libsource (lib "eagle-import") (part "R-US_R0402"))
    )
    (comp (ref "R77")
      (value "100k")
      (footprint "eagle-import:R0402")
      (libsource (lib "eagle-import") (part "R-US_R0402"))
    )
    (comp (ref "C34")
      (value "47p")
      (footprint "eagle-import:C0402")
      (libsource (lib "eagle-import") (part "C-USC0402"))
    )
    (comp (ref "C35")
      (value "47p")
      (footprint "eagle-import:C0402")
      (libsource (lib "eagle-import") (part "C-USC0402"))
    )
    (comp (ref "C37")
      (value "100n")
      (footprint "eagle-import:C0402")
      (libsource (lib "eagle-import") (part "C-USC0402"))
    )
    (comp (ref "C39")
      (value "100n")
      (footprint "eagle-import:C0402")
      (libsource (lib "eagle-import") (part "C-USC0402"))
    )
    (comp (ref "C43")
      (value "47p")
      (footprint "eagle-import:C0402")
      (libsource (lib "eagle-import") (part "C-USC0402"))
    )
    (comp (ref "C44")
      (value "47p")
      (footprint "eagle-import:C0402")
      (libsource (lib "eagle-import") (part "C-USC0402"))
    )
    (comp (ref "C48")
      (value "100n")
      (footprint "eagle-import:C0402")
      (libsource (lib "eagle-import") (part "C-USC0402"))
    )
    (comp (ref "C49")
      (value "100n")
      (footprint "eagle-import:C0402")
      (libsource (lib "eagle-import") (part "C-USC0402"))
    )
    (comp (ref "C50")
      (value "100n")
      (footprint "eagle-import:C0402")
      (libsource (lib "eagle-import") (part "C-USC0402"))
    )
    (comp (ref "C51")
      (value "470n")
      (footprint "eagle-import:C0402")
      (libsource (lib "eagle-import") (part "C-USC0402"))
    )
    (comp (ref "IC7")
      (value "OPA4171")
      (footprint "eagle-import:TSSOP14_065")
      (libsource (lib "eagle-import") (part "TL074PW"))
    )
    (comp (ref "IC9")
      (value "LM324PW")
      (footprint "eagle-import:TSSOP14_065")
      (libsource (lib "eagle-import") (part "TL074PW"))
    )
    (comp (ref "IC10")
      (value "TL074PW")
      (footprint "eagle-import:TSSOP14_065")
      (libsource (lib "eagle-import") (part "TL074PW"))
    )
    (comp (ref "J10")
      (value "PJ301_THONKICONN6")
      (footprint "eagle-import:WQP_PJ_301M6")
      (libsource (lib "eagle-import") (part "PJ301_THONKICONN6"))
    )
    (comp (ref "J11")
      (value "PJ301_THONKICONN6")
      (footprint "eagle-import:WQP_PJ_301M6")
      (libsource (lib "eagle-import") (part "PJ301_THONKICONN6"))
    )
    (comp (ref "J12")
      (value "PJ301_THONKICONN6")
      (footprint "eagle-import:WQP_PJ_301M6")
      (libsource (lib "eagle-import") (part "PJ301_THONKICONN6"))
    )
    (comp (ref "J13")
      (value "PJ301_THONKICONN6")
      (footprint "eagle-import:WQP_PJ_301M6")
      (libsource (lib "eagle-import") (part "PJ301_THONKICONN6"))
    )
    (comp (ref "J14")
      (value "PJ301_THONKICONN6")
      (footprint "eagle-import:WQP_PJ_301M6")
      (libsource (lib "eagle-import") (part "PJ301_THONKICONN6"))
    )
    (comp (ref "J15")
      (value "PJ301_THONKICONN6")
      (footprint "eagle-import:WQP_PJ_301M6")
      (libsource (lib "eagle-import") (part "PJ301_THONKICONN6"))
    )
    (comp (ref "J16")
      (value "PJ301_THONKICONN6")
      (footprint "eagle-import:WQP_PJ_301M6")
      (libsource (lib "eagle-import") (part "PJ301_THONKICONN6"))
    )
    (comp (ref "LED6")
      (value "WP937EGW")
      (footprint "eagle-import:LED3MM")
      (libsource (lib "eagle-import") (part "LED-BICOLOR-SHARED-THROUGHHOLE"))
    )
    (comp (ref "LED7")
      (value "WP937EGW")
      (footprint "eagle-import:LED3MM")
      (libsource (lib "eagle-import") (part "LED-BICOLOR-SHARED-THROUGHHOLE"))
    )
    (comp (ref "LED8")
      (value "WP937EGW")
      (footprint "eagle-import:LED3MM")
      (libsource (lib "eagle-import") (part "LED-BICOLOR-SHARED-THROUGHHOLE"))
    )
    (comp (ref "LED9")
      (value "WP937EGW")
      (footprint "eagle-import:LED3MM")
      (libsource (lib "eagle-import") (part "LED-BICOLOR-SHARED-THROUGHHOLE"))
    )
    (comp (ref "LED10")
      (value "WP937EGW")
      (footprint "eagle-import:LED3MM")
      (libsource (lib "eagle-import") (part "LED-BICOLOR-SHARED-THROUGHHOLE"))
    )
    (comp (ref "LED11")
      (value "WP937EGW")
      (footprint "eagle-import:LED3MM")
      (libsource (lib "eagle-import") (part "LED-BICOLOR-SHARED-THROUGHHOLE"))
    )
    (comp (ref "LED12")
      (value "WP937EGW")
      (footprint "eagle-import:LED3MM")
      (libsource (lib "eagle-import") (part "LED-BICOLOR-SHARED-THROUGHHOLE"))
    )
    (comp (ref "R43")
      (value "100k")
      (footprint "eagle-import:R0402")
      (libsource (lib "eagle-import") (part "R-US_R0402"))
    )
    (comp (ref "R44")
      (value "100k")
      (footprint "eagle-import:R0402")
      (libsource (lib "eagle-import") (part "R-US_R0402"))
    )
    (comp (ref "R45")
      (value "1.0k")
      (footprint "eagle-import:R0603")
      (libsource (lib "eagle-import") (part "R-US_R0603"))
    )
    (comp (ref "R46")
      (value "1.0k")
      (footprint "eagle-import:R0603")
      (libsource (lib "eagle-import") (part "R-US_R0603"))
    )
    (comp (ref "R47")
      (value "23.7k")
      (footprint "eagle-import:R0402")
      (libsource (lib "eagle-import") (part "R-US_R0402"))
    )
    (comp (ref "R48")
      (value "23.7k")
      (footprint "eagle-import:R0402")
      (libsource (lib "eagle-import") (part "R-US_R0402"))
    )
    (comp (ref "R49")
      (value "39k")
      (footprint "eagle-import:R0402")
      (libsource (lib "eagle-import") (part "R-US_R0402"))
    )
    (comp (ref "R50")
      (value "39k")
      (footprint "eagle-import:R0402")
      (libsource (lib "eagle-import") (part "R-US_R0402"))
    )
    (comp (ref "R51")
      (value "56k")
      (footprint "eagle-import:R0402")
      (libsource (lib "eagle-import") (part "R-US_R0402"))
    )
    (comp (ref "R52")
      (value "56k")
      (footprint "eagle-import:R0402")
      (libsource (lib "eagle-import") (part "R-US_R0402"))
    )
    (comp (ref "R53")
      (value "23.7k")
      (footprint "eagle-import:R0402")
      (libsource (lib "eagle-import") (part "R-US_R0402"))
    )
    (comp (ref "R54")
      (value "23.7k")
      (footprint "eagle-import:R0402")
      (libsource (lib "eagle-import") (part "R-US_R0402"))
    )
    (comp (ref "R55")
      (value "10k")
      (footprint "eagle-import:R0402")
      (libsource (lib "eagle-import") (part "R-US_R0402"))
    )
    (comp (ref "R56")
      (value "10k")
      (footprint "eagle-import:R0402")
      (libsource (lib "eagle-import") (part "R-US_R0402"))
    )
    (comp (ref "R60")
      (value "100k")
      (footprint "eagle-import:R0402")
      (libsource (lib "eagle-import") (part "R-US_R0402"))
    )
    (comp (ref "R61")
      (value "100k")
      (footprint "eagle-import:R0402")
      (libsource (lib "eagle-import") (part "R-US_R0402"))
    )
    (comp (ref "R62")
      (value "1.0k")
      (footprint "eagle-import:R0603")
      (libsource (lib "eagle-import") (part "R-US_R0603"))
    )
    (comp (ref "R63")
      (value "1.0k")
      (footprint "eagle-import:R0603")
      (libsource (lib "eagle-import") (part "R-US_R0603"))
    )
    (comp (ref "R67")
      (value "10k")
      (footprint "eagle-import:R0402")
      (libsource (lib "eagle-import") (part "R-US_R0402"))
    )
    (comp (ref "R69")
      (value "56k")
      (footprint "eagle-import:R0402")
      (libsource (lib "eagle-import") (part "R-US_R0402"))
    )
    (comp (ref "R73")
      (value "100k")
      (footprint "eagle-import:R0402")
      (libsource (lib "eagle-import") (part "R-US_R0402"))
    )
    (comp (ref "R74")
      (value "150k")
      (footprint "eagle-import:R0402")
      (libsource (lib "eagle-import") (part "R-US_R0402"))
    )
    (comp (ref "R75")
      (value "39k")
      (footprint "eagle-import:R0402")
      (libsource (lib "eagle-import") (part "R-US_R0402"))
    )
    (comp (ref "R78")
      (value "680")
      (footprint "eagle-import:R0402")
      (libsource (lib "eagle-import") (part "R-US_R0402"))
    )
    (comp (ref "R79")
      (value "680")
      (footprint "eagle-import:R0402")
      (libsource (lib "eagle-import") (part "R-US_R0402"))
    )
    (comp (ref "R80")
      (value "680")
      (footprint "eagle-import:R0402")
      (libsource (lib "eagle-import") (part "R-US_R0402"))
    )
    (comp (ref "R81")
      (value "680")
      (footprint "eagle-import:R0402")
      (libsource (lib "eagle-import") (part "R-US_R0402"))
    )
    (comp (ref "R82")
      (value "180")
      (footprint "eagle-import:R0402")
      (libsource (lib "eagle-import") (part "R-US_R0402"))
    )
    (comp (ref "R83")
      (value "180")
      (footprint "eagle-import:R0402")
      (libsource (lib "eagle-import") (part "R-US_R0402"))
    )
    (comp (ref "R84")
      (value "180")
      (footprint "eagle-import:R0402")
      (libsource (lib "eagle-import") (part "R-US_R0402"))
    )
    (comp (ref "R85")
      (value "1.0k")
      (footprint "eagle-import:R0603")
      (libsource (lib "eagle-import") (part "R-US_R0603"))
    )
    (comp (ref "R86")
      (value "1.0k")
      (footprint "eagle-import:R0603")
      (libsource (lib "eagle-import") (part "R-US_R0603"))
    )
    (comp (ref "R87")
      (value "1.0k")
      (footprint "eagle-import:R0603")
      (libsource (lib "eagle-import") (part "R-US_R0603"))
    )
  )
  (nets
    (net (code "1") (name "+3V3") (class "Default")
      (node (ref "C1") (pin "1") (pinfunction "1_1") (pintype "passive"))
      (node (ref "C12") (pin "1") (pinfunction "1_1") (pintype "passive"))
      (node (ref "C13") (pin "1") (pinfunction "1_1") (pintype "passive"))
      (node (ref "C16") (pin "1") (pinfunction "1_1") (pintype "passive"))
      (node (ref "C19") (pin "1") (pinfunction "1_1") (pintype "passive"))
      (node (ref "C2") (pin "+") (pinfunction "+_+") (pintype "passive"))
      (node (ref "C21") (pin "1") (pinfunction "1_1") (pintype "passive"))
      (node (ref "D3") (pin "2") (pinfunction "C_2") (pintype "passive"))
      (node (ref "IC1") (pin "3") (pinfunction "VO_3") (pintype "passive"))
      (node (ref "IC2") (pin "1") (pinfunction "VBAT_1") (pintype "power_in"))
      (node (ref "IC2") (pin "19") (pinfunction "VDD_4_19") (pintype "power_in"))
      (node (ref "IC2") (pin "32") (pinfunction "VDD_1_32") (pintype "power_in"))
      (node (ref "IC2") (pin "48") (pinfunction "VDD_2_48") (pintype "power_in"))
      (node (ref "IC2") (pin "64") (pinfunction "VDD_3_64") (pintype "power_in"))
      (node (ref "IC4") (pin "12") (pinfunction "DVDD_12") (pintype "power_in"))
      (node (ref "R22") (pin "2") (pinfunction "2_2") (pintype "passive"))
      (node (ref "R23") (pin "2") (pinfunction "2_2") (pintype "passive"))
      (node (ref "R6") (pin "2") (pinfunction "2_2") (pintype "passive"))
    )
    (net (code "2") (name "+3V3_A") (class "Default")
      (node (ref "C10") (pin "1") (pinfunction "1_1") (pintype "passive"))
      (node (ref "C23") (pin "+") (pinfunction "+_+") (pintype "passive"))
      (node (ref "C26") (pin "1") (pinfunction "1_1") (pintype "passive"))
      (node (ref "C27") (pin "+") (pinfunction "+_+") (pintype "passive"))
      (node (ref "C46") (pin "1") (pinfunction "1_1") (pintype "passive"))
      (node (ref "C47") (pin "1") (pinfunction "1_1") (pintype "passive"))
      (node (ref "C9") (pin "1") (pinfunction "1_1") (pintype "passive"))
      (node (ref "IC2") (pin "13") (pinfunction "VDDA_13") (pintype "power_in"))
      (node (ref "IC3") (pin "1") (pinfunction "VO_1") (pintype "passive"))
      (node (ref "IC4") (pin "4") (pinfunction "AVDD_4") (pintype "power_in"))
      (node (ref "IC5") (pin "4") (pinfunction "V+_4") (pintype "power_in"))
      (node (ref "IC6") (pin "4") (pinfunction "V+_4") (pintype "power_in"))
      (node (ref "R13") (pin "P$1") (pinfunction "E_P$1") (pintype "passive"))
      (node (ref "R14") (pin "P$1") (pinfunction "E_P$1") (pintype "passive"))
      (node (ref "R16") (pin "P$1") (pinfunction "E_P$1") (pintype "passive"))
      (node (ref "R20") (pin "P$1") (pinfunction "E_P$1") (pintype "passive"))
      (node (ref "R21") (pin "P$1") (pinfunction "E_P$1") (pintype "passive"))
      (node (ref "R37") (pin "P$1") (pinfunction "E_P$1") (pintype "passive"))
      (node (ref "R38") (pin "P$1") (pinfunction "E_P$1") (pintype "passive"))
      (node (ref "R4") (pin "P$1") (pinfunction "E_P$1") (pintype "passive"))
    )
    (net (code "3") (name "ADC_DV_CV") (class "Default")
      (node (ref "C33") (pin "2") (pinfunction "2_2") (pintype "passive"))
      (node (ref "IC2") (pin "21") (pinfunction "PA5/SPI1_SCK/ADC5/DAC2_21") (pintype "bidirectional"))
      (node (ref "IC6") (pin "8") (pinfunction "OUT_8") (pintype "output"))
      (node (ref "R42") (pin "1") (pinfunction "1_1") (pintype "passive"))
    )
    (net (code "4") (name "ADC_DV_POT") (class "Default")
      (node (ref "C8") (pin "1") (pinfunction "1_1") (pintype "passive"))
      (node (ref "IC2") (pin "11") (pinfunction "PC3/SPI2_MOSI/I2S2_SD/ADC13_11") (pintype "bidirectional"))
      (node (ref "R4") (pin "P$2") (pinfunction "S_P$2") (pintype "passive"))
    )
    (net (code "5") (name "ADC_LENGTH_POT") (class "Default")
      (node (ref "C24") (pin "1") (pinfunction "1_1") (pintype "passive"))
      (node (ref "IC2") (pin "27") (pinfunction "PB1/ADC9/TIM3_CH4_27") (pintype "bidirectional"))
      (node (ref "R16") (pin "P$2") (pinfunction "S_P$2") (pintype "passive"))
    )
    (net (code "6") (name "ADC_T_BIAS_CV") (class "Default")
      (node (ref "C40") (pin "2") (pinfunction "2_2") (pintype "passive"))
      (node (ref "IC2") (pin "15") (pinfunction "PA1/USART2_RTS/UART4_RX/ADC1/TIM2_CH2_15") (pintype "bidirectional"))
      (node (ref "IC5") (pin "1") (pinfunction "OUT_1") (pintype "output"))
      (node (ref "R57") (pin "1") (pinfunction "1_1") (pintype "passive"))
    )
    (net (code "7") (name "ADC_T_BIAS_POT") (class "Default")
      (node (ref "C28") (pin "1") (pinfunction "1_1") (pintype "passive"))
      (node (ref "IC2") (pin "16") (pinfunction "PA2/USART2_TX/ADC2/TIM2_CH3_16") (pintype "bidirectional"))
      (node (ref "R20") (pin "P$2") (pinfunction "S_P$2") (pintype "passive"))
    )
    (net (code "8") (name "ADC_T_JITTER_CV") (class "Default")
      (node (ref "C42") (pin "2") (pinfunction "2_2") (pintype "passive"))
      (node (ref "IC2") (pin "20") (pinfunction "PA4/SPI1_NSS/SPI3_NSS/USART2_CK/I2S3_WS/ADC4/DAC1_20") (pintype "bidirectional"))
      (node (ref "IC6") (pin "7") (pinfunction "OUT_7") (pintype "output"))
      (node (ref "R59") (pin "1") (pinfunction "1_1") (pintype "passive"))
    )
    (net (code "9") (name "ADC_T_JITTER_POT") (class "Default")
      (node (ref "C38") (pin "1") (pinfunction "1_1") (pintype "passive"))
      (node (ref "IC2") (pin "25") (pinfunction "PC5/ADC15_25") (pintype "bidirectional"))
      (node (ref "R37") (pin "P$2") (pinfunction "S_P$2") (pintype "passive"))
    )
    (net (code "10") (name "ADC_T_RATE_CV") (class "Default")
      (node (ref "C41") (pin "2") (pinfunction "2_2") (pintype "passive"))
      (node (ref "IC2") (pin "17") (pinfunction "PA3/USART2_RX/ADC3/TIM2_CH4_17") (pintype "bidirectional"))
      (node (ref "IC6") (pin "1") (pinfunction "OUT_1") (pintype "output"))
      (node (ref "R58") (pin "1") (pinfunction "1_1") (pintype "passive"))
    )
    (net (code "11") (name "ADC_T_RATE_POT") (class "Default")
      (node (ref "C17") (pin "1") (pinfunction "1_1") (pintype "passive"))
      (node (ref "IC2") (pin "10") (pinfunction "PC2/SPI2_MISO/ADC12_10") (pintype "bidirectional"))
      (node (ref "R13") (pin "P$2") (pinfunction "S_P$2") (pintype "passive"))
    )
    (net (code "12") (name "ADC_X_BIAS_CV") (class "Default")
      (node (ref "C30") (pin "2") (pinfunction "2_2") (pintype "passive"))
      (node (ref "IC2") (pin "24") (pinfunction "PC4/ADC14_24") (pintype "bidirectional"))
      (node (ref "IC5") (pin "14") (pinfunction "OUT_14") (pintype "output"))
      (node (ref "R39") (pin "1") (pinfunction "1_1") (pintype "passive"))
    )
    (net (code "13") (name "ADC_X_BIAS_POT") (class "Default")
      (node (ref "C29") (pin "1") (pinfunction "1_1") (pintype "passive"))
      (node (ref "IC2") (pin "9") (pinfunction "PC1/ADC11_9") (pintype "bidirectional"))
      (node (ref "R21") (pin "P$2") (pinfunction "S_P$2") (pintype "passive"))
    )
    (net (code "14") (name "ADC_X_SPREAD_CV") (class "Default")
      (node (ref "C31") (pin "2") (pinfunction "2_2") (pintype "passive"))
      (node (ref "IC2") (pin "14") (pinfunction "PA0-WKUP/USART2_CTS/UART4_TX/ADC0/TIM2_CH1_ETR_14") (pintype "bidirectional"))
      (node (ref "IC2") (pin "23") (pinfunction "PA7/SPI1_MOSI/ADC7/TIM3_CH2_23") (pintype "bidirectional"))
      (node (ref "IC5") (pin "8") (pinfunction "OUT_8") (pintype "output"))
      (node (ref "R40") (pin "1") (pinfunction "1_1") (pintype "passive"))
    )
    (net (code "15") (name "ADC_X_SPREAD_POT") (class "Default")
      (node (ref "C18") (pin "1") (pinfunction "1_1") (pintype "passive"))
      (node (ref "IC2") (pin "8") (pinfunction "PC0/ADC10_8") (pintype "bidirectional"))
      (node (ref "R14") (pin "P$2") (pinfunction "S_P$2") (pintype "passive"))
    )
    (net (code "16") (name "ADC_X_STEPS_CV") (class "Default")
      (node (ref "C32") (pin "2") (pinfunction "2_2") (pintype "passive"))
      (node (ref "IC2") (pin "22") (pinfunction "PA6/SPI1_MISO/ADC6/TIM3_CH1_22") (pintype "bidirectional"))
      (node (ref "IC6") (pin "14") (pinfunction "OUT_14") (pintype "output"))
      (node (ref "R41") (pin "1") (pinfunction "1_1") (pintype "passive"))
    )
    (net (code "17") (name "ADC_X_STEPS_POT") (class "Default")
      (node (ref "C36") (pin "1") (pinfunction "1_1") (pintype "passive"))
      (node (ref "IC2") (pin "26") (pinfunction "PB0/ADC8/TIM3_CH3_26") (pintype "bidirectional"))
      (node (ref "R38") (pin "P$2") (pinfunction "S_P$2") (pintype "passive"))
    )
    (net (code "18") (name "AREF_-10") (class "Default")
      (node (ref "C52") (pin "1") (pinfunction "1_1") (pintype "passive"))
      (node (ref "IC8") (pin "2") (pinfunction "A_2") (pintype "passive"))
      (node (ref "R28") (pin "2") (pinfunction "2_2") (pintype "passive"))
      (node (ref "R29") (pin "2") (pinfunction "2_2") (pintype "passive"))
      (node (ref "R30") (pin "2") (pinfunction "2_2") (pintype "passive"))
      (node (ref "R31") (pin "2") (pinfunction "2_2") (pintype "passive"))
      (node (ref "R68") (pin "2") (pinfunction "2_2") (pintype "passive"))
      (node (ref "R70") (pin "2") (pinfunction "2_2") (pintype "passive"))
      (node (ref "R71") (pin "2") (pinfunction "2_2") (pintype "passive"))
      (node (ref "R72") (pin "2") (pinfunction "2_2") (pintype "passive"))
    )
    (net (code "19") (name "DAC_MOSI") (class "Default")
      (node (ref "IC2") (pin "53") (pinfunction "PC12/UART5_TX/I2S3_SD/USART3_CK_53") (pintype "bidirectional"))
      (node (ref "IC4") (pin "11") (pinfunction "IN_11") (pintype "input"))
    )
    (net (code "20") (name "DAC_SCK") (class "Default")
      (node (ref "IC2") (pin "51") (pinfunction "PC10/SPI3_SCK/I2S3_SCK/UART4_TX_51") (pintype "bidirectional"))
      (node (ref "IC4") (pin "10") (pinfunction "SCK_10") (pintype "input"))
    )
    (net (code "21") (name "DAC_SS") (class "Default")
      (node (ref "IC2") (pin "50") (pinfunction "PA15/JTDI/SPI3_NSS/I2S3_WS_50") (pintype "bidirectional"))
      (node (ref "IC4") (pin "9") (pinfunction "SYNC_9") (pintype "input"))
    )
    (net (code "22") (name "DAC_X_1") (class "Default")
      (node (ref "IC4") (pin "2") (pinfunction "OUTB_2") (pintype "output"))
      (node (ref "R47") (pin "2") (pinfunction "2_2") (pintype "passive"))
    )
    (net (code "23") (name "DAC_X_2") (class "Default")
      (node (ref "IC4") (pin "7") (pinfunction "OUTC_7") (pintype "output"))
      (node (ref "R48") (pin "2") (pinfunction "2_2") (pintype "passive"))
    )
    (net (code "24") (name "DAC_X_3") (class "Default")
      (node (ref "IC4") (pin "8") (pinfunction "OUTD_8") (pintype "output"))
      (node (ref "R53") (pin "2") (pinfunction "2_2") (pintype "passive"))
    )
    (net (code "25") (name "DAC_Y") (class "Default")
      (node (ref "IC4") (pin "1") (pinfunction "OUTA_1") (pintype "output"))
      (node (ref "R54") (pin "2") (pinfunction "2_2") (pintype "passive"))
    )
    (net (code "26") (name "DEPRECATED") (class "Default")
      (node (ref "IC5") (pin "6") (pinfunction "-IN_6") (pintype "input"))
      (node (ref "IC5") (pin "7") (pinfunction "OUT_7") (pintype "output"))
    )
    (net (code "27") (name "GATE_T_1") (class "Default")
      (node (ref "IC2") (pin "52") (pinfunction "PC11/UART4_RX/SPI3_MISO/USART3_RX_52") (pintype "bidirectional"))
      (node (ref "LED6") (pin "1") (pinfunction "1_1") (pintype "bidirectional"))
      (node (ref "R56") (pin "2") (pinfunction "2_2") (pintype "passive"))
    )
    (net (code "28") (name "GATE_T_2") (class "Default")
      (node (ref "IC2") (pin "44") (pinfunction "PA11/USART1_CTS/CANRX/USBDM/TIM1_CH4_44") (pintype "bidirectional"))
      (node (ref "LED7") (pin "1") (pinfunction "1_1") (pintype "bidirectional"))
      (node (ref "R55") (pin "2") (pinfunction "2_2") (pintype "passive"))
    )
    (net (code "29") (name "GATE_T_3") (class "Default")
      (node (ref "IC2") (pin "45") (pinfunction "PA12/USART1_RTS/CANTX/USBDP/TIM1_ETR_45") (pintype "bidirectional"))
      (node (ref "LED8") (pin "1") (pinfunction "1_1") (pintype "bidirectional"))
      (node (ref "R67") (pin "2") (pinfunction "2_2") (pintype "passive"))
    )
    (net (code "30") (name "GND") (class "Default")
      (node (ref "C1") (pin "2") (pinfunction "2_2") (pintype "passive"))
      (node (ref "C10") (pin "2") (pinfunction "2_2") (pintype "passive"))
      (node (ref "C11") (pin "-") (pinfunction "-_-") (pintype "passive"))
      (node (ref "C12") (pin "2") (pinfunction "2_2") (pintype "passive"))
      (node (ref "C13") (pin "2") (pinfunction "2_2") (pintype "passive"))
      (node (ref "C14") (pin "2") (pinfunction "2_2") (pintype "passive"))
      (node (ref "C15") (pin "2") (pinfunction "2_2") (pintype "passive"))
      (node (ref "C16") (pin "2") (pinfunction "2_2") (pintype "passive"))
      (node (ref "C17") (pin "2") (pinfunction "2_2") (pintype "passive"))
      (node (ref "C18") (pin "2") (pinfunction "2_2") (pintype "passive"))
      (node (ref "C19") (pin "2") (pinfunction "2_2") (pintype "passive"))
      (node (ref "C2") (pin "-") (pinfunction "-_-") (pintype "passive"))
      (node (ref "C20") (pin "2") (pinfunction "2_2") (pintype "passive"))
      (node (ref "C21") (pin "2") (pinfunction "2_2") (pintype "passive"))
      (node (ref "C22") (pin "+") (pinfunction "+_+") (pintype "passive"))
      (node (ref "C23") (pin "-") (pinfunction "-_-") (pintype "passive"))
      (node (ref "C24") (pin "2") (pinfunction "2_2") (pintype "passive"))
      (node (ref "C25") (pin "2") (pinfunction "2_2") (pintype "passive"))
      (node (ref "C26") (pin "2") (pinfunction "2_2") (pintype "passive"))
      (node (ref "C27") (pin "-") (pinfunction "-_-") (pintype "passive"))
      (node (ref "C28") (pin "2") (pinfunction "2_2") (pintype "passive"))
      (node (ref "C29") (pin "2") (pinfunction "2_2") (pintype "passive"))
      (node (ref "C3") (pin "2") (pinfunction "2_2") (pintype "passive"))
      (node (ref "C36") (pin "2") (pinfunction "2_2") (pintype "passive"))
      (node (ref "C37") (pin "1") (pinfunction "1_1") (pintype "passive"))
      (node (ref "C38") (pin "2") (pinfunction "2_2") (pintype "passive"))
      (node (ref "C39") (pin "2") (pinfunction "2_2") (pintype "passive"))
      (node (ref "C4") (pin "1") (pinfunction "1_1") (pintype "passive"))
      (node (ref "C45") (pin "2") (pinfunction "2_2") (pintype "passive"))
      (node (ref "C46") (pin "2") (pinfunction "2_2") (pintype "passive"))
      (node (ref "C47") (pin "2") (pinfunction "2_2") (pintype "passive"))
      (node (ref "C48") (pin "2") (pinfunction "2_2") (pintype "passive"))
      (node (ref "C49") (pin "1") (pinfunction "1_1") (pintype "passive"))
      (node (ref "C5") (pin "2") (pinfunction "2_2") (pintype "passive"))
      (node (ref "C50") (pin "2") (pinfunction "2_2") (pintype "passive"))
      (node (ref "C51") (pin "2") (pinfunction "2_2") (pintype "passive"))
      (node (ref "C52") (pin "2") (pinfunction "2_2") (pintype "passive"))
      (node (ref "C53") (pin "2") (pinfunction "2_2") (pintype "passive"))
      (node (ref "C54") (pin "2") (pinfunction "2_2") (pintype "passive"))
      (node (ref "C55") (pin "2") (pinfunction "2_2") (pintype "passive"))
      (node (ref "C56") (pin "2") (pinfunction "2_2") (pintype "passive"))
      (node (ref "C57") (pin "2") (pinfunction "2_2") (pintype "passive"))
      (node (ref "C58") (pin "2") (pinfunction "2_2") (pintype "passive"))
      (node (ref "C6") (pin "1") (pinfunction "1_1") (pintype "passive"))
      (node (ref "C7") (pin "2") (pinfunction "2_2") (pintype "passive"))
      (node (ref "C8") (pin "2") (pinfunction "2_2") (pintype "passive"))
      (node (ref "C9") (pin "2") (pinfunction "2_2") (pintype "passive"))
      (node (ref "D3") (pin "1") (pinfunction "A_1") (pintype "passive"))
      (node (ref "D4") (pin "A") (pinfunction "A_A") (pintype "passive"))
      (node (ref "D5") (pin "A") (pinfunction "A_A") (pintype "passive"))
      (node (ref "IC1") (pin "2") (pinfunction "GND_2") (pintype "passive"))
      (node (ref "IC2") (pin "12") (pinfunction "VSSA_12") (pintype "power_in"))
      (node (ref "IC2") (pin "18") (pinfunction "VSS_4_18") (pintype "power_in"))
      (node (ref "IC2") (pin "28") (pinfunction "PB2/BOOT1_28") (pintype "bidirectional"))
      (node (ref "IC2") (pin "60") (pinfunction "BOOT0_60") (pintype "bidirectional"))
      (node (ref "IC2") (pin "63") (pinfunction "VSS_3_63") (pintype "power_in"))
      (node (ref "IC3") (pin "2") (pinfunction "GND_2") (pintype "passive"))
      (node (ref "IC4") (pin "13") (pinfunction "A0_13") (pintype "input"))
      (node (ref "IC4") (pin "14") (pinfunction "A1_14") (pintype "input"))
      (node (ref "IC4") (pin "15") (pinfunction "ENABLE_15") (pintype "input"))
      (node (ref "IC4") (pin "16") (pinfunction "LDAC_16") (pintype "input"))
      (node (ref "IC4") (pin "5") (pinfunction "VREFL_5") (pintype "bidirectional"))
      (node (ref "IC4") (pin "6") (pinfunction "GND_6") (pintype "power_in"))
      (node (ref "IC5") (pin "10") (pinfunction "+IN_10") (pintype "input"))
      (node (ref "IC5") (pin "11") (pinfunction "V-_11") (pintype "power_in"))
      (node (ref "IC5") (pin "12") (pinfunction "+IN_12") (pintype "input"))
      (node (ref "IC5") (pin "3") (pinfunction "+IN_3") (pintype "input"))
      (node (ref "IC5") (pin "5") (pinfunction "+IN_5") (pintype "input"))
      (node (ref "IC6") (pin "10") (pinfunction "+IN_10") (pintype "input"))
      (node (ref "IC6") (pin "11") (pinfunction "V-_11") (pintype "power_in"))
      (node (ref "IC6") (pin "12") (pinfunction "+IN_12") (pintype "input"))
      (node (ref "IC6") (pin "3") (pinfunction "+IN_3") (pintype "input"))
      (node (ref "IC6") (pin "5") (pinfunction "+IN_5") (pintype "input"))
      (node (ref "IC8") (pin "1") (pinfunction "C_1") (pintype "passive"))
      (node (ref "IC9") (pin "11") (pinfunction "V-_11") (pintype "power_in"))
      (node (ref "IC9") (pin "5") (pinfunction "+IN_5") (pintype "input"))
      (node (ref "J1") (pin "P1") (pinfunction "1_P1") (pintype "passive"))
      (node (ref "J1") (pin "P2") (pinfunction "2_P2") (pintype "passive"))
      (node (ref "J10") (pin "P1") (pinfunction "1_P1") (pintype "passive"))
      (node (ref "J11") (pin "P1") (pinfunction "1_P1") (pintype "passive"))
      (node (ref "J12") (pin "P1") (pinfunction "1_P1") (pintype "passive"))
      (node (ref "J13") (pin "P1") (pinfunction "1_P1") (pintype "passive"))
      (node (ref "J14") (pin "P1") (pinfunction "1_P1") (pintype "passive"))
      (node (ref "J15") (pin "P1") (pinfunction "1_P1") (pintype "passive"))
      (node (ref "J16") (pin "P1") (pinfunction "1_P1") (pintype "passive"))
      (node (ref "J2") (pin "P1") (pinfunction "1_P1") (pintype "passive"))
      (node (ref "J2") (pin "P2") (pinfunction "2_P2") (pintype "passive"))
      (node (ref "J3") (pin "P1") (pinfunction "1_P1") (pintype "passive"))
      (node (ref "J4") (pin "P1") (pinfunction "1_P1") (pintype "passive"))
      (node (ref "J4") (pin "P2") (pinfunction "2_P2") (pintype "passive"))
      (node (ref "J5") (pin "P1") (pinfunction "1_P1") (pintype "passive"))
      (node (ref "J5") (pin "P2") (pinfunction "2_P2") (pintype "passive"))
      (node (ref "J6") (pin "P1") (pinfunction "1_P1") (pintype "passive"))
      (node (ref "J6") (pin "P2") (pinfunction "2_P2") (pintype "passive"))
      (node (ref "J7") (pin "P1") (pinfunction "1_P1") (pintype "passive"))
      (node (ref "J7") (pin "P2") (pinfunction "2_P2") (pintype "passive"))
      (node (ref "J8") (pin "P1") (pinfunction "1_P1") (pintype "passive"))
      (node (ref "J8") (pin "P2") (pinfunction "2_P2") (pintype "passive"))
      (node (ref "J9") (pin "P1") (pinfunction "1_P1") (pintype "passive"))
      (node (ref "JP1") (pin "1") (pinfunction "1_1") (pintype "passive"))
      (node (ref "JP4") (pin "3") (pinfunction "3_3") (pintype "passive"))
      (node (ref "JP4") (pin "4") (pinfunction "4_4") (pintype "passive"))
      (node (ref "JP4") (pin "5") (pinfunction "5_5") (pintype "passive"))
      (node (ref "JP4") (pin "6") (pinfunction "6_6") (pintype "passive"))
      (node (ref "JP4") (pin "7") (pinfunction "7_7") (pintype "passive"))
      (node (ref "JP4") (pin "8") (pinfunction "8_8") (pintype "passive"))
      (node (ref "LED1") (pin "2") (pinfunction "C_2") (pintype "bidirectional"))
      (node (ref "LED2") (pin "2") (pinfunction "C_2") (pintype "bidirectional"))
      (node (ref "LED3") (pin "2") (pinfunction "C_2") (pintype "bidirectional"))
      (node (ref "LED4") (pin "2") (pinfunction "C_2") (pintype "bidirectional"))
      (node (ref "LED5") (pin "2") (pinfunction "C_2") (pintype "bidirectional"))
      (node (ref "Q1") (pin "2") (pinfunction "LID1_2") (pintype "power_in"))
      (node (ref "Q1") (pin "4") (pinfunction "LID2_4") (pintype "power_in"))
      (node (ref "Q2") (pin "E") (pinfunction "E_E") (pintype "passive"))
      (node (ref "Q3") (pin "E") (pinfunction "E_E") (pintype "passive"))
      (node (ref "R13") (pin "P$3") (pinfunction "A_P$3") (pintype "passive"))
      (node (ref "R14") (pin "P$3") (pinfunction "A_P$3") (pintype "passive"))
      (node (ref "R16") (pin "P$3") (pinfunction "A_P$3") (pintype "passive"))
      (node (ref "R20") (pin "P$3") (pinfunction "A_P$3") (pintype "passive"))
      (node (ref "R21") (pin "P$3") (pinfunction "A_P$3") (pintype "passive"))
      (node (ref "R24") (pin "1") (pinfunction "1_1") (pintype "passive"))
      (node (ref "R25") (pin "1") (pinfunction "1_1") (pintype "passive"))
      (node (ref "R37") (pin "P$3") (pinfunction "A_P$3") (pintype "passive"))
      (node (ref "R38") (pin "P$3") (pinfunction "A_P$3") (pintype "passive"))
      (node (ref "R4") (pin "P$3") (pinfunction "A_P$3") (pintype "passive"))
      (node (ref "R49") (pin "2") (pinfunction "2_2") (pintype "passive"))
      (node (ref "R50") (pin "2") (pinfunction "2_2") (pintype "passive"))
      (node (ref "R73") (pin "1") (pinfunction "1_1") (pintype "passive"))
      (node (ref "R75") (pin "2") (pinfunction "2_2") (pintype "passive"))
      (node (ref "R78") (pin "2") (pinfunction "2_2") (pintype "passive"))
      (node (ref "R79") (pin "2") (pinfunction "2_2") (pintype "passive"))
      (node (ref "R80") (pin "2") (pinfunction "2_2") (pintype "passive"))
      (node (ref "R81") (pin "2") (pinfunction "2_2") (pintype "passive"))
      (node (ref "R82") (pin "1") (pinfunction "1_1") (pintype "passive"))
      (node (ref "R83") (pin "1") (pinfunction "1_1") (pintype "passive"))
      (node (ref "R84") (pin "1") (pinfunction "1_1") (pintype "passive"))
      (node (ref "SW1") (pin "L2") (pinfunction "L2_L2") (pintype "passive"))
      (node (ref "SW1") (pin "P3") (pinfunction "A3_P3") (pintype "passive"))
      (node (ref "SW1") (pin "P6") (pinfunction "B3_P6") (pintype "passive"))
      (node (ref "SW2") (pin "L2") (pinfunction "L2_L2") (pintype "passive"))
      (node (ref "SW2") (pin "P3") (pinfunction "A3_P3") (pintype "passive"))
      (node (ref "SW2") (pin "P6") (pinfunction "B3_P6") (pintype "passive"))
      (node (ref "SW3") (pin "1") (pinfunction "1_1") (pintype "passive"))
      (node (ref "SW3") (pin "2") (pinfunction "2_2") (pintype "passive"))
      (node (ref "SW4") (pin "1") (pinfunction "1_1") (pintype "passive"))
      (node (ref "SW4") (pin "2") (pinfunction "2_2") (pintype "passive"))
      (node (ref "SW5") (pin "1") (pinfunction "1_1") (pintype "passive"))
      (node (ref "SW5") (pin "2") (pinfunction "2_2") (pintype "passive"))
      (node (ref "SW6") (pin "1") (pinfunction "1_1") (pintype "passive"))
      (node (ref "SW6") (pin "2") (pinfunction "2_2") (pintype "passive"))
      (node (ref "SW7") (pin "1") (pinfunction "1_1") (pintype "passive"))
      (node (ref "SW7") (pin "2") (pinfunction "2_2") (pintype "passive"))
    )
    (net (code "31") (name "LED_T_DV") (class "Default")
      (node (ref "IC2") (pin "29") (pinfunction "PB10/SPI2_SCK/I2S_SCK/I2C2_SCL/USART3_TX_29") (pintype "bidirectional"))
      (node (ref "R1") (pin "1") (pinfunction "1_1") (pintype "passive"))
    )
    (net (code "32") (name "LED_T_MODE_G") (class "Default")
      (node (ref "IC2") (pin "33") (pinfunction "PB12/SPI2_NSS/I2S2_WS/I2C2_SMBA/USART3_CK/TIM1_BKIN_33") (pintype "bidirectional"))
      (node (ref "R10") (pin "1") (pinfunction "1_1") (pintype "passive"))
    )
    (net (code "33") (name "LED_T_MODE_R") (class "Default")
      (node (ref "IC2") (pin "34") (pinfunction "PB13/SPI2_SCK/I2S2_SCK/USART3_CTS/TIM1_CH1N_34") (pintype "bidirectional"))
      (node (ref "R9") (pin "1") (pinfunction "1_1") (pintype "passive"))
    )
    (net (code "34") (name "LED_T_RANGE_G") (class "Default")
      (node (ref "IC2") (pin "37") (pinfunction "PC6/I2S2_MCK_37") (pintype "bidirectional"))
      (node (ref "R18") (pin "1") (pinfunction "1_1") (pintype "passive"))
    )
    (net (code "35") (name "LED_T_RANGE_R") (class "Default")
      (node (ref "IC2") (pin "38") (pinfunction "PC7/I2S3_MCK_38") (pintype "bidirectional"))
      (node (ref "R19") (pin "1") (pinfunction "1_1") (pintype "passive"))
    )
    (net (code "36") (name "LED_X_DV") (class "Default")
      (node (ref "IC2") (pin "62") (pinfunction "PB9/SPI2_NSS/I2S2_WS/I2C1_SDA/TIM4_CH4_62") (pintype "bidirectional"))
      (node (ref "R5") (pin "1") (pinfunction "1_1") (pintype "passive"))
    )
    (net (code "37") (name "LED_X_EXT_G") (class "Default")
      (node (ref "IC2") (pin "55") (pinfunction "PB3/JTDO/SPI3_SCK/I2S3_SCK_55") (pintype "bidirectional"))
      (node (ref "R36") (pin "1") (pinfunction "1_1") (pintype "passive"))
    )
    (net (code "38") (name "LED_X_MODE_G") (class "Default")
      (node (ref "IC2") (pin "59") (pinfunction "PB7/I2C1_SDA/TIM4_CH2/USART1_RX_59") (pintype "bidirectional"))
      (node (ref "R12") (pin "1") (pinfunction "1_1") (pintype "passive"))
    )
    (net (code "39") (name "LED_X_MODE_R") (class "Default")
      (node (ref "IC2") (pin "61") (pinfunction "PB8/TIM4_CH3/I2C1_SCL_61") (pintype "bidirectional"))
      (node (ref "R11") (pin "1") (pinfunction "1_1") (pintype "passive"))
    )
    (net (code "40") (name "LED_X_RANGE_G") (class "Default")
      (node (ref "IC2") (pin "57") (pinfunction "PB5/I2C1_SMBA/SPI1_MOSI/SPI3_MOSI/I2S3_SD_57") (pintype "bidirectional"))
      (node (ref "R17") (pin "1") (pinfunction "1_1") (pintype "passive"))
    )
    (net (code "41") (name "LED_X_RANGE_R") (class "Default")
      (node (ref "IC2") (pin "56") (pinfunction "PB4/NJTRST/SPI3_MISO/SPI1_MISO_56") (pintype "bidirectional"))
      (node (ref "R15") (pin "1") (pinfunction "1_1") (pintype "passive"))
    )
    (net (code "42") (name "NORMALIZATION_PROBE") (class "Default")
      (node (ref "D3") (pin "3") (pinfunction "AC_3") (pintype "passive"))
      (node (ref "IC2") (pin "39") (pinfunction "PC8_39") (pintype "bidirectional"))
      (node (ref "R76") (pin "1") (pinfunction "1_1") (pintype "passive"))
      (node (ref "R77") (pin "1") (pinfunction "1_1") (pintype "passive"))
    )
    (net (code "43") (name "Net-(C5-Pad1)") (class "Default")
      (node (ref "C5") (pin "1") (pinfunction "1_1") (pintype "passive"))
      (node (ref "D1") (pin "C") (pinfunction "C_C") (pintype "passive"))
      (node (ref "L1") (pin "1") (pinfunction "1_1") (pintype "passive"))
      (node (ref "L2") (pin "2") (pinfunction "2_2") (pintype "passive"))
      (node (ref "L3") (pin "2") (pinfunction "2_2") (pintype "passive"))
    )
    (net (code "44") (name "Net-(C6-Pad2)") (class "Default")
      (node (ref "C6") (pin "2") (pinfunction "2_2") (pintype "passive"))
      (node (ref "Q1") (pin "1") (pinfunction "1_1") (pintype "passive"))
      (node (ref "R7") (pin "2") (pinfunction "2_2") (pintype "passive"))
    )
    (net (code "45") (name "Net-(D1-PadA)") (class "Default")
      (node (ref "D1") (pin "A") (pinfunction "A_A") (pintype "passive"))
      (node (ref "JP4") (pin "10") (pinfunction "10_10") (pintype "passive"))
      (node (ref "JP4") (pin "9") (pinfunction "9_9") (pintype "passive"))
    )
    (net (code "46") (name "Net-(D2-PadA)") (class "Default")
      (node (ref "D2") (pin "A") (pinfunction "A_A") (pintype "passive"))
      (node (ref "L4") (pin "2") (pinfunction "2_2") (pintype "passive"))
    )
    (net (code "47") (name "Net-(D2-PadC)") (class "Default")
      (node (ref "D2") (pin "C") (pinfunction "C_C") (pintype "passive"))
      (node (ref "JP4") (pin "1") (pinfunction "1_1") (pintype "passive"))
      (node (ref "JP4") (pin "2") (pinfunction "2_2") (pintype "passive"))
    )
    (net (code "48") (name "Net-(D4-PadC)") (class "Default")
      (node (ref "D4") (pin "C") (pinfunction "C_C") (pintype "passive"))
      (node (ref "Q2") (pin "B") (pinfunction "B_B") (pintype "passive"))
      (node (ref "R24") (pin "2") (pinfunction "2_2") (pintype "passive"))
      (node (ref "R26") (pin "2") (pinfunction "2_2") (pintype "passive"))
    )
    (net (code "49") (name "Net-(D5-PadC)") (class "Default")
      (node (ref "D5") (pin "C") (pinfunction "C_C") (pintype "passive"))
      (node (ref "Q3") (pin "B") (pinfunction "B_B") (pintype "passive"))
      (node (ref "R25") (pin "2") (pinfunction "2_2") (pintype "passive"))
      (node (ref "R27") (pin "2") (pinfunction "2_2") (pintype "passive"))
    )
    (net (code "50") (name "Net-(IC1-VI)") (class "Default")
      (node (ref "C3") (pin "1") (pinfunction "1_1") (pintype "passive"))
      (node (ref "IC1") (pin "1") (pinfunction "VI_1") (pintype "input"))
      (node (ref "L1") (pin "2") (pinfunction "2_2") (pintype "passive"))
    )
    (net (code "51") (name "Net-(IC2-PD0{slash}OSC_IN)") (class "Default")
      (node (ref "IC2") (pin "5") (pinfunction "PD0/OSC_IN_5") (pintype "bidirectional"))
      (node (ref "R8") (pin "1") (pinfunction "1_1") (pintype "passive"))
    )
    (net (code "52") (name "Net-(IC2-PD1{slash}OSC_OUT)") (class "Default")
      (node (ref "IC2") (pin "6") (pinfunction "PD1/OSC_OUT_6") (pintype "bidirectional"))
      (node (ref "R7") (pin "1") (pinfunction "1_1") (pintype "passive"))
    )
    (net (code "53") (name "Net-(IC2-VCAP_1)") (class "Default")
      (node (ref "C15") (pin "1") (pinfunction "1_1") (pintype "passive"))
      (node (ref "IC2") (pin "31") (pinfunction "VCAP_1_31") (pintype "power_in"))
    )
    (net (code "54") (name "Net-(IC2-VCAP_2)") (class "Default")
      (node (ref "C20") (pin "1") (pinfunction "1_1") (pintype "passive"))
      (node (ref "IC2") (pin "47") (pinfunction "VCAP_2_47") (pintype "power_in"))
    )
    (net (code "55") (name "Net-(IC3-VI)") (class "Default")
      (node (ref "C14") (pin "1") (pinfunction "1_1") (pintype "passive"))
      (node (ref "IC3") (pin "3") (pinfunction "VI_3") (pintype "input"))
      (node (ref "L3") (pin "1") (pinfunction "1_1") (pintype "passive"))
    )
    (net (code "56") (name "Net-(IC5A--IN)") (class "Default")
      (node (ref "C40") (pin "1") (pinfunction "1_1") (pintype "passive"))
      (node (ref "IC5") (pin "2") (pinfunction "-IN_2") (pintype "input"))
      (node (ref "R57") (pin "2") (pinfunction "2_2") (pintype "passive"))
      (node (ref "R64") (pin "1") (pinfunction "1_1") (pintype "passive"))
      (node (ref "R70") (pin "1") (pinfunction "1_1") (pintype "passive"))
    )
    (net (code "57") (name "Net-(IC5C--IN)") (class "Default")
      (node (ref "C31") (pin "1") (pinfunction "1_1") (pintype "passive"))
      (node (ref "IC5") (pin "9") (pinfunction "-IN_9") (pintype "input"))
      (node (ref "R28") (pin "1") (pinfunction "1_1") (pintype "passive"))
      (node (ref "R34") (pin "1") (pinfunction "1_1") (pintype "passive"))
      (node (ref "R40") (pin "2") (pinfunction "2_2") (pintype "passive"))
    )
    (net (code "58") (name "Net-(IC5D--IN)") (class "Default")
      (node (ref "C30") (pin "1") (pinfunction "1_1") (pintype "passive"))
      (node (ref "IC5") (pin "13") (pinfunction "-IN_13") (pintype "input"))
      (node (ref "R30") (pin "1") (pinfunction "1_1") (pintype "passive"))
      (node (ref "R33") (pin "1") (pinfunction "1_1") (pintype "passive"))
      (node (ref "R39") (pin "2") (pinfunction "2_2") (pintype "passive"))
    )
    (net (code "59") (name "Net-(IC6A--IN)") (class "Default")
      (node (ref "C41") (pin "1") (pinfunction "1_1") (pintype "passive"))
      (node (ref "IC6") (pin "2") (pinfunction "-IN_2") (pintype "input"))
      (node (ref "R58") (pin "2") (pinfunction "2_2") (pintype "passive"))
      (node (ref "R65") (pin "1") (pinfunction "1_1") (pintype "passive"))
      (node (ref "R71") (pin "1") (pinfunction "1_1") (pintype "passive"))
    )
    (net (code "60") (name "Net-(IC6B--IN)") (class "Default")
      (node (ref "C42") (pin "1") (pinfunction "1_1") (pintype "passive"))
      (node (ref "IC6") (pin "6") (pinfunction "-IN_6") (pintype "input"))
      (node (ref "R59") (pin "2") (pinfunction "2_2") (pintype "passive"))
      (node (ref "R66") (pin "1") (pinfunction "1_1") (pintype "passive"))
      (node (ref "R72") (pin "1") (pinfunction "1_1") (pintype "passive"))
    )
    (net (code "61") (name "Net-(IC6C--IN)") (class "Default")
      (node (ref "C33") (pin "1") (pinfunction "1_1") (pintype "passive"))
      (node (ref "IC6") (pin "9") (pinfunction "-IN_9") (pintype "input"))
      (node (ref "R31") (pin "1") (pinfunction "1_1") (pintype "passive"))
      (node (ref "R32") (pin "1") (pinfunction "1_1") (pintype "passive"))
      (node (ref "R42") (pin "2") (pinfunction "2_2") (pintype "passive"))
    )
    (net (code "62") (name "Net-(IC6D--IN)") (class "Default")
      (node (ref "C32") (pin "1") (pinfunction "1_1") (pintype "passive"))
      (node (ref "IC6") (pin "13") (pinfunction "-IN_13") (pintype "input"))
      (node (ref "R29") (pin "1") (pinfunction "1_1") (pintype "passive"))
      (node (ref "R35") (pin "1") (pinfunction "1_1") (pintype "passive"))
      (node (ref "R41") (pin "2") (pinfunction "2_2") (pintype "passive"))
    )
    (net (code "63") (name "Net-(IC7A--IN)") (class "Default")
      (node (ref "C34") (pin "1") (pinfunction "1_1") (pintype "passive"))
      (node (ref "IC7") (pin "2") (pinfunction "-IN_2") (pintype "input"))
      (node (ref "R43") (pin "2") (pinfunction "2_2") (pintype "passive"))
      (node (ref "R47") (pin "1") (pinfunction "1_1") (pintype "passive"))
    )
    (net (code "64") (name "Net-(IC7B--IN)") (class "Default")
      (node (ref "C43") (pin "1") (pinfunction "1_1") (pintype "passive"))
      (node (ref "IC7") (pin "6") (pinfunction "-IN_6") (pintype "input"))
      (node (ref "R54") (pin "1") (pinfunction "1_1") (pintype "passive"))
      (node (ref "R60") (pin "2") (pinfunction "2_2") (pintype "passive"))
    )
    (net (code "65") (name "Net-(IC7C--IN)") (class "Default")
      (node (ref "C44") (pin "1") (pinfunction "1_1") (pintype "passive"))
      (node (ref "IC7") (pin "9") (pinfunction "-IN_9") (pintype "input"))
      (node (ref "R53") (pin "1") (pinfunction "1_1") (pintype "passive"))
      (node (ref "R61") (pin "2") (pinfunction "2_2") (pintype "passive"))
    )
    (net (code "66") (name "Net-(IC7D--IN)") (class "Default")
      (node (ref "C35") (pin "1") (pinfunction "1_1") (pintype "passive"))
      (node (ref "IC7") (pin "13") (pinfunction "-IN_13") (pintype "input"))
      (node (ref "R44") (pin "2") (pinfunction "2_2") (pintype "passive"))
      (node (ref "R48") (pin "1") (pinfunction "1_1") (pintype "passive"))
    )
    (net (code "67") (name "Net-(IC9A-+IN)") (class "Default")
      (node (ref "IC9") (pin "3") (pinfunction "+IN_3") (pintype "input"))
      (node (ref "R56") (pin "1") (pinfunction "1_1") (pintype "passive"))
    )
    (net (code "68") (name "Net-(IC9A--IN)") (class "Default")
      (node (ref "IC9") (pin "2") (pinfunction "-IN_2") (pintype "input"))
      (node (ref "R50") (pin "1") (pinfunction "1_1") (pintype "passive"))
      (node (ref "R51") (pin "2") (pinfunction "2_2") (pintype "passive"))
    )
    (net (code "69") (name "Net-(IC9A-OUT)") (class "Default")
      (node (ref "IC9") (pin "1") (pinfunction "OUT_1") (pintype "output"))
      (node (ref "R51") (pin "1") (pinfunction "1_1") (pintype "passive"))
      (node (ref "R85") (pin "2") (pinfunction "2_2") (pintype "passive"))
    )
    (net (code "70") (name "Net-(IC9B--IN)") (class "Default")
      (node (ref "IC9") (pin "6") (pinfunction "-IN_6") (pintype "input"))
      (node (ref "IC9") (pin "7") (pinfunction "OUT_7") (pintype "output"))
    )
    (net (code "71") (name "Net-(IC9C-+IN)") (class "Default")
      (node (ref "IC9") (pin "10") (pinfunction "+IN_10") (pintype "input"))
      (node (ref "R67") (pin "1") (pinfunction "1_1") (pintype "passive"))
    )
    (net (code "72") (name "Net-(IC9C--IN)") (class "Default")
      (node (ref "IC9") (pin "9") (pinfunction "-IN_9") (pintype "input"))
      (node (ref "R69") (pin "2") (pinfunction "2_2") (pintype "passive"))
      (node (ref "R75") (pin "1") (pinfunction "1_1") (pintype "passive"))
    )
    (net (code "73") (name "Net-(IC9C-OUT)") (class "Default")
      (node (ref "IC9") (pin "8") (pinfunction "OUT_8") (pintype "output"))
      (node (ref "R69") (pin "1") (pinfunction "1_1") (pintype "passive"))
      (node (ref "R87") (pin "2") (pinfunction "2_2") (pintype "passive"))
    )
    (net (code "74") (name "Net-(IC9D-+IN)") (class "Default")
      (node (ref "IC9") (pin "12") (pinfunction "+IN_12") (pintype "input"))
      (node (ref "R55") (pin "1") (pinfunction "1_1") (pintype "passive"))
    )
    (net (code "75") (name "Net-(IC9D--IN)") (class "Default")
      (node (ref "IC9") (pin "13") (pinfunction "-IN_13") (pintype "input"))
      (node (ref "R49") (pin "1") (pinfunction "1_1") (pintype "passive"))
      (node (ref "R52") (pin "2") (pinfunction "2_2") (pintype "passive"))
    )
    (net (code "76") (name "Net-(IC9D-OUT)") (class "Default")
      (node (ref "IC9") (pin "14") (pinfunction "OUT_14") (pintype "output"))
      (node (ref "R52") (pin "1") (pinfunction "1_1") (pintype "passive"))
      (node (ref "R86") (pin "2") (pinfunction "2_2") (pintype "passive"))
    )
    (net (code "77") (name "Net-(IC10A-+IN)") (class "Default")
      (node (ref "C34") (pin "2") (pinfunction "2_2") (pintype "passive"))
      (node (ref "IC10") (pin "3") (pinfunction "+IN_3") (pintype "input"))
      (node (ref "IC7") (pin "1") (pinfunction "OUT_1") (pintype "output"))
      (node (ref "R45") (pin "2") (pinfunction "2_2") (pintype "passive"))
    )
    (net (code "78") (name "Net-(IC10A--IN)") (class "Default")
      (node (ref "IC10") (pin "2") (pinfunction "-IN_2") (pintype "input"))
      (node (ref "LED10") (pin "2") (pinfunction "2_2") (pintype "bidirectional"))
      (node (ref "R79") (pin "1") (pinfunction "1_1") (pintype "passive"))
    )
    (net (code "79") (name "Net-(IC10A-OUT)") (class "Default")
      (node (ref "IC10") (pin "1") (pinfunction "OUT_1") (pintype "output"))
      (node (ref "LED10") (pin "1") (pinfunction "1_1") (pintype "bidirectional"))
    )
    (net (code "80") (name "Net-(IC10B-+IN)") (class "Default")
      (node (ref "C43") (pin "2") (pinfunction "2_2") (pintype "passive"))
      (node (ref "IC10") (pin "5") (pinfunction "+IN_5") (pintype "input"))
      (node (ref "IC7") (pin "7") (pinfunction "OUT_7") (pintype "output"))
      (node (ref "R62") (pin "2") (pinfunction "2_2") (pintype "passive"))
    )
    (net (code "81") (name "Net-(IC10B--IN)") (class "Default")
      (node (ref "IC10") (pin "6") (pinfunction "-IN_6") (pintype "input"))
      (node (ref "LED9") (pin "2") (pinfunction "2_2") (pintype "bidirectional"))
      (node (ref "R78") (pin "1") (pinfunction "1_1") (pintype "passive"))
    )
    (net (code "82") (name "Net-(IC10B-OUT)") (class "Default")
      (node (ref "IC10") (pin "7") (pinfunction "OUT_7") (pintype "output"))
      (node (ref "LED9") (pin "1") (pinfunction "1_1") (pintype "bidirectional"))
    )
    (net (code "83") (name "Net-(IC10C-+IN)") (class "Default")
      (node (ref "C44") (pin "2") (pinfunction "2_2") (pintype "passive"))
      (node (ref "IC10") (pin "10") (pinfunction "+IN_10") (pintype "input"))
      (node (ref "IC7") (pin "8") (pinfunction "OUT_8") (pintype "output"))
      (node (ref "R63") (pin "2") (pinfunction "2_2") (pintype "passive"))
    )
    (net (code "84") (name "Net-(IC10C--IN)") (class "Default")
      (node (ref "IC10") (pin "9") (pinfunction "-IN_9") (pintype "input"))
      (node (ref "LED12") (pin "2") (pinfunction "2_2") (pintype "bidirectional"))
      (node (ref "R81") (pin "1") (pinfunction "1_1") (pintype "passive"))
    )
    (net (code "85") (name "Net-(IC10C-OUT)") (class "Default")
      (node (ref "IC10") (pin "8") (pinfunction "OUT_8") (pintype "output"))
      (node (ref "LED12") (pin "1") (pinfunction "1_1") (pintype "bidirectional"))
    )
    (net (code "86") (name "Net-(IC10D-+IN)") (class "Default")
      (node (ref "C35") (pin "2") (pinfunction "2_2") (pintype "passive"))
      (node (ref "IC10") (pin "12") (pinfunction "+IN_12") (pintype "input"))
      (node (ref "IC7") (pin "14") (pinfunction "OUT_14") (pintype "output"))
      (node (ref "R46") (pin "2") (pinfunction "2_2") (pintype "passive"))
    )
    (net (code "87") (name "Net-(IC10D--IN)") (class "Default")
      (node (ref "IC10") (pin "13") (pinfunction "-IN_13") (pintype "input"))
      (node (ref "LED11") (pin "2") (pinfunction "2_2") (pintype "bidirectional"))
      (node (ref "R80") (pin "1") (pinfunction "1_1") (pintype "passive"))
    )
    (net (code "88") (name "Net-(IC10D-OUT)") (class "Default")
      (node (ref "IC10") (pin "14") (pinfunction "OUT_14") (pintype "output"))
      (node (ref "LED11") (pin "1") (pinfunction "1_1") (pintype "bidirectional"))
    )
    (net (code "89") (name "Net-(J1-3)") (class "Default")
      (node (ref "C53") (pin "1") (pinfunction "1_1") (pintype "passive"))
      (node (ref "J1") (pin "P3") (pinfunction "3_P3") (pintype "passive"))
      (node (ref "R64") (pin "2") (pinfunction "2_2") (pintype "passive"))
    )
    (net (code "90") (name "Net-(J2-3)") (class "Default")
      (node (ref "C45") (pin "1") (pinfunction "1_1") (pintype "passive"))
      (node (ref "J2") (pin "P3") (pinfunction "3_P3") (pintype "passive"))
      (node (ref "R33") (pin "2") (pinfunction "2_2") (pintype "passive"))
    )
    (net (code "91") (name "Net-(J3-2)") (class "Default")
      (node (ref "J3") (pin "P2") (pinfunction "2_P2") (pintype "passive"))
      (node (ref "R76") (pin "2") (pinfunction "2_2") (pintype "passive"))
    )
    (net (code "92") (name "Net-(J3-3)") (class "Default")
      (node (ref "J3") (pin "P3") (pinfunction "3_P3") (pintype "passive"))
      (node (ref "R26") (pin "1") (pinfunction "1_1") (pintype "passive"))
    )
    (net (code "93") (name "Net-(J4-3)") (class "Default")
      (node (ref "C56") (pin "1") (pinfunction "1_1") (pintype "passive"))
      (node (ref "J4") (pin "P3") (pinfunction "3_P3") (pintype "passive"))
      (node (ref "R65") (pin "2") (pinfunction "2_2") (pintype "passive"))
    )
    (net (code "94") (name "Net-(J5-3)") (class "Default")
      (node (ref "C58") (pin "1") (pinfunction "1_1") (pintype "passive"))
      (node (ref "J5") (pin "P3") (pinfunction "3_P3") (pintype "passive"))
      (node (ref "R66") (pin "2") (pinfunction "2_2") (pintype "passive"))
    )
    (net (code "95") (name "Net-(J6-3)") (class "Default")
      (node (ref "C54") (pin "1") (pinfunction "1_1") (pintype "passive"))
      (node (ref "J6") (pin "P3") (pinfunction "3_P3") (pintype "passive"))
      (node (ref "R32") (pin "2") (pinfunction "2_2") (pintype "passive"))
    )
    (net (code "96") (name "Net-(J7-3)") (class "Default")
      (node (ref "C55") (pin "1") (pinfunction "1_1") (pintype "passive"))
      (node (ref "J7") (pin "P3") (pinfunction "3_P3") (pintype "passive"))
      (node (ref "R35") (pin "2") (pinfunction "2_2") (pintype "passive"))
    )
    (net (code "97") (name "Net-(J8-3)") (class "Default")
      (node (ref "C57") (pin "1") (pinfunction "1_1") (pintype "passive"))
      (node (ref "J8") (pin "P3") (pinfunction "3_P3") (pintype "passive"))
      (node (ref "R34") (pin "2") (pinfunction "2_2") (pintype "passive"))
    )
    (net (code "98") (name "Net-(J9-2)") (class "Default")
      (node (ref "J9") (pin "P2") (pinfunction "2_P2") (pintype "passive"))
      (node (ref "R77") (pin "2") (pinfunction "2_2") (pintype "passive"))
    )
    (net (code "99") (name "Net-(J9-3)") (class "Default")
      (node (ref "J9") (pin "P3") (pinfunction "3_P3") (pintype "passive"))
      (node (ref "R27") (pin "1") (pinfunction "1_1") (pintype "passive"))
    )
    (net (code "100") (name "Net-(J10-3)") (class "Default")
      (node (ref "J10") (pin "P3") (pinfunction "3_P3") (pintype "passive"))
      (node (ref "R85") (pin "1") (pinfunction "1_1") (pintype "passive"))
    )
    (net (code "101") (name "Net-(J11-3)") (class "Default")
      (node (ref "J11") (pin "P3") (pinfunction "3_P3") (pintype "passive"))
      (node (ref "R86") (pin "1") (pinfunction "1_1") (pintype "passive"))
    )
    (net (code "102") (name "Net-(J12-3)") (class "Default")
      (node (ref "J12") (pin "P3") (pinfunction "3_P3") (pintype "passive"))
      (node (ref "R87") (pin "1") (pinfunction "1_1") (pintype "passive"))
    )
    (net (code "103") (name "Net-(J13-3)") (class "Default")
      (node (ref "J13") (pin "P3") (pinfunction "3_P3") (pintype "passive"))
      (node (ref "R60") (pin "1") (pinfunction "1_1") (pintype "passive"))
      (node (ref "R62") (pin "1") (pinfunction "1_1") (pintype "passive"))
    )
    (net (code "104") (name "Net-(J14-3)") (class "Default")
      (node (ref "J14") (pin "P3") (pinfunction "3_P3") (pintype "passive"))
      (node (ref "R43") (pin "1") (pinfunction "1_1") (pintype "passive"))
      (node (ref "R45") (pin "1") (pinfunction "1_1") (pintype "passive"))
    )
    (net (code "105") (name "Net-(J15-3)") (class "Default")
      (node (ref "J15") (pin "P3") (pinfunction "3_P3") (pintype "passive"))
      (node (ref "R44") (pin "1") (pinfunction "1_1") (pintype "passive"))
      (node (ref "R46") (pin "1") (pinfunction "1_1") (pintype "passive"))
    )
    (net (code "106") (name "Net-(J16-3)") (class "Default")
      (node (ref "J16") (pin "P3") (pinfunction "3_P3") (pintype "passive"))
      (node (ref "R61") (pin "1") (pinfunction "1_1") (pintype "passive"))
      (node (ref "R63") (pin "1") (pinfunction "1_1") (pintype "passive"))
    )
    (net (code "107") (name "Net-(JP2-Pad1)") (class "Default")
      (node (ref "JP2") (pin "1") (pinfunction "1_1") (pintype "passive"))
      (node (ref "R3") (pin "1") (pinfunction "1_1") (pintype "passive"))
    )
    (net (code "108") (name "Net-(JP2-Pad2)") (class "Default")
      (node (ref "JP2") (pin "2") (pinfunction "2_2") (pintype "passive"))
      (node (ref "R2") (pin "1") (pinfunction "1_1") (pintype "passive"))
    )
    (net (code "109") (name "Net-(LED1-GRN)") (class "Default")
      (node (ref "LED1") (pin "1") (pinfunction "GRN_1") (pintype "bidirectional"))
      (node (ref "R10") (pin "2") (pinfunction "2_2") (pintype "passive"))
    )
    (net (code "110") (name "Net-(LED1-RED)") (class "Default")
      (node (ref "LED1") (pin "3") (pinfunction "RED_3") (pintype "bidirectional"))
      (node (ref "R9") (pin "2") (pinfunction "2_2") (pintype "passive"))
    )
    (net (code "111") (name "Net-(LED2-GRN)") (class "Default")
      (node (ref "LED2") (pin "1") (pinfunction "GRN_1") (pintype "bidirectional"))
      (node (ref "R12") (pin "2") (pinfunction "2_2") (pintype "passive"))
    )
    (net (code "112") (name "Net-(LED2-RED)") (class "Default")
      (node (ref "LED2") (pin "3") (pinfunction "RED_3") (pintype "bidirectional"))
      (node (ref "R11") (pin "2") (pinfunction "2_2") (pintype "passive"))
    )
    (net (code "113") (name "Net-(LED3-GRN)") (class "Default")
      (node (ref "LED3") (pin "1") (pinfunction "GRN_1") (pintype "bidirectional"))
      (node (ref "R18") (pin "2") (pinfunction "2_2") (pintype "passive"))
    )
    (net (code "114") (name "Net-(LED3-RED)") (class "Default")
      (node (ref "LED3") (pin "3") (pinfunction "RED_3") (pintype "bidirectional"))
      (node (ref "R19") (pin "2") (pinfunction "2_2") (pintype "passive"))
    )
    (net (code "115") (name "Net-(LED4-GRN)") (class "Default")
      (node (ref "LED4") (pin "1") (pinfunction "GRN_1") (pintype "bidirectional"))
      (node (ref "R17") (pin "2") (pinfunction "2_2") (pintype "passive"))
    )
    (net (code "116") (name "Net-(LED4-RED)") (class "Default")
      (node (ref "LED4") (pin "3") (pinfunction "RED_3") (pintype "bidirectional"))
      (node (ref "R15") (pin "2") (pinfunction "2_2") (pintype "passive"))
    )
    (net (code "117") (name "Net-(LED5-GRN)") (class "Default")
      (node (ref "LED5") (pin "1") (pinfunction "GRN_1") (pintype "bidirectional"))
      (node (ref "R36") (pin "2") (pinfunction "2_2") (pintype "passive"))
    )
    (net (code "118") (name "Net-(LED6-Pad2)") (class "Default")
      (node (ref "LED6") (pin "2") (pinfunction "2_2") (pintype "bidirectional"))
      (node (ref "R82") (pin "2") (pinfunction "2_2") (pintype "passive"))
    )
    (net (code "119") (name "Net-(LED7-Pad2)") (class "Default")
      (node (ref "LED7") (pin "2") (pinfunction "2_2") (pintype "bidirectional"))
      (node (ref "R83") (pin "2") (pinfunction "2_2") (pintype "passive"))
    )
    (net (code "120") (name "Net-(LED8-Pad2)") (class "Default")
      (node (ref "LED8") (pin "2") (pinfunction "2_2") (pintype "bidirectional"))
      (node (ref "R84") (pin "2") (pinfunction "2_2") (pintype "passive"))
    )
    (net (code "121") (name "Net-(Q1B-2)") (class "Default")
      (node (ref "C4") (pin "2") (pinfunction "2_2") (pintype "passive"))
      (node (ref "Q1") (pin "3") (pinfunction "2_3") (pintype "passive"))
      (node (ref "R8") (pin "2") (pinfunction "2_2") (pintype "passive"))
    )
    (net (code "122") (name "Net-(R1-Pad2)") (class "Default")
      (node (ref "R1") (pin "2") (pinfunction "2_2") (pintype "passive"))
      (node (ref "SW1") (pin "L1") (pinfunction "L1_L1") (pintype "passive"))
    )
    (net (code "123") (name "Net-(R5-Pad2)") (class "Default")
      (node (ref "R5") (pin "2") (pinfunction "2_2") (pintype "passive"))
      (node (ref "SW2") (pin "L1") (pinfunction "L1_L1") (pintype "passive"))
    )
    (net (code "124") (name "RESET") (class "Default")
      (node (ref "C7") (pin "1") (pinfunction "1_1") (pintype "passive"))
      (node (ref "IC2") (pin "7") (pinfunction "NRST_7") (pintype "bidirectional"))
      (node (ref "JP1") (pin "4") (pinfunction "4_4") (pintype "passive"))
      (node (ref "R6") (pin "1") (pinfunction "1_1") (pintype "passive"))
    )
    (net (code "125") (name "RX") (class "Default")
      (node (ref "IC2") (pin "43") (pinfunction "PA10/USART1_RX/TIM1_CH3_43") (pintype "bidirectional"))
      (node (ref "R3") (pin "2") (pinfunction "2_2") (pintype "passive"))
    )
    (net (code "126") (name "SWCLK") (class "Default")
      (node (ref "IC2") (pin "49") (pinfunction "PA14/JTCK-SWCLK_49") (pintype "bidirectional"))
      (node (ref "JP1") (pin "3") (pinfunction "3_3") (pintype "passive"))
    )
    (net (code "127") (name "SWDIO") (class "Default")
      (node (ref "IC2") (pin "46") (pinfunction "PA13/JTMS-SWDAT_46") (pintype "bidirectional"))
      (node (ref "JP1") (pin "2") (pinfunction "2_2") (pintype "passive"))
    )
    (net (code "128") (name "SW_T_DV") (class "Default")
      (node (ref "IC2") (pin "30") (pinfunction "PB11/I2C2_SDA/USART3_RX_30") (pintype "bidirectional"))
      (node (ref "SW1") (pin "P2") (pinfunction "A2_P2") (pintype "passive"))
      (node (ref "SW1") (pin "P5") (pinfunction "B2_P5") (pintype "passive"))
    )
    (net (code "129") (name "SW_T_MODE") (class "Default")
      (node (ref "IC2") (pin "35") (pinfunction "PB14/SPI2_MISO/USART3_RTS/TIM1_CH2N_35") (pintype "bidirectional"))
      (node (ref "SW3") (pin "3") (pinfunction "3_3") (pintype "passive"))
      (node (ref "SW3") (pin "4") (pinfunction "4_4") (pintype "passive"))
    )
    (net (code "130") (name "SW_T_RANGE") (class "Default")
      (node (ref "IC2") (pin "36") (pinfunction "PB15/SPI2_MOSI/I2S2_SD/TIM1_CH3N_36") (pintype "bidirectional"))
      (node (ref "SW5") (pin "3") (pinfunction "3_3") (pintype "passive"))
      (node (ref "SW5") (pin "4") (pinfunction "4_4") (pintype "passive"))
    )
    (net (code "131") (name "SW_X_DV") (class "Default")
      (node (ref "IC2") (pin "4") (pinfunction "PC15/OSC_OUT_4") (pintype "bidirectional"))
      (node (ref "SW2") (pin "P2") (pinfunction "A2_P2") (pintype "passive"))
      (node (ref "SW2") (pin "P5") (pinfunction "B2_P5") (pintype "passive"))
    )
    (net (code "132") (name "SW_X_EXT") (class "Default")
      (node (ref "IC2") (pin "54") (pinfunction "PD2/TIM3-ETR_54") (pintype "bidirectional"))
      (node (ref "SW7") (pin "3") (pinfunction "3_3") (pintype "passive"))
      (node (ref "SW7") (pin "4") (pinfunction "4_4") (pintype "passive"))
    )
    (net (code "133") (name "SW_X_MODE") (class "Default")
      (node (ref "IC2") (pin "2") (pinfunction "PC13-TAMPER-RTC_2") (pintype "bidirectional"))
      (node (ref "SW4") (pin "3") (pinfunction "3_3") (pintype "passive"))
      (node (ref "SW4") (pin "4") (pinfunction "4_4") (pintype "passive"))
    )
    (net (code "134") (name "SW_X_RANGE") (class "Default")
      (node (ref "IC2") (pin "58") (pinfunction "PB6/I2C1_SCL/TIM4_CH1/USART1_TX_58") (pintype "bidirectional"))
      (node (ref "SW6") (pin "3") (pinfunction "3_3") (pintype "passive"))
      (node (ref "SW6") (pin "4") (pinfunction "4_4") (pintype "passive"))
    )
    (net (code "135") (name "TX") (class "Default")
      (node (ref "IC2") (pin "42") (pinfunction "PA9/USART1_TX/TIM1_CH2_42") (pintype "bidirectional"))
      (node (ref "R2") (pin "2") (pinfunction "2_2") (pintype "passive"))
    )
    (net (code "136") (name "T_CLOCK") (class "Default")
      (node (ref "IC2") (pin "40") (pinfunction "PC9/I2S2_CKIN/I2S3_CKIN_40") (pintype "bidirectional"))
      (node (ref "Q2") (pin "C") (pinfunction "C_C") (pintype "passive"))
      (node (ref "R22") (pin "1") (pinfunction "1_1") (pintype "passive"))
    )
    (net (code "137") (name "VCC") (class "Default")
      (node (ref "C11") (pin "+") (pinfunction "+_+") (pintype "passive"))
      (node (ref "C39") (pin "1") (pinfunction "1_1") (pintype "passive"))
      (node (ref "C48") (pin "1") (pinfunction "1_1") (pintype "passive"))
      (node (ref "C50") (pin "1") (pinfunction "1_1") (pintype "passive"))
      (node (ref "IC10") (pin "4") (pinfunction "V+_4") (pintype "power_in"))
      (node (ref "IC7") (pin "4") (pinfunction "V+_4") (pintype "power_in"))
      (node (ref "IC9") (pin "4") (pinfunction "V+_4") (pintype "power_in"))
      (node (ref "L2") (pin "1") (pinfunction "1_1") (pintype "passive"))
    )
    (net (code "138") (name "VEE") (class "Default")
      (node (ref "C22") (pin "-") (pinfunction "-_-") (pintype "passive"))
      (node (ref "C37") (pin "2") (pinfunction "2_2") (pintype "passive"))
      (node (ref "C49") (pin "2") (pinfunction "2_2") (pintype "passive"))
      (node (ref "IC10") (pin "11") (pinfunction "V-_11") (pintype "power_in"))
      (node (ref "IC7") (pin "11") (pinfunction "V-_11") (pintype "power_in"))
      (node (ref "L4") (pin "1") (pinfunction "1_1") (pintype "passive"))
      (node (ref "R68") (pin "1") (pinfunction "1_1") (pintype "passive"))
    )
    (net (code "139") (name "VREF") (class "Default")
      (node (ref "C25") (pin "1") (pinfunction "1_1") (pintype "passive"))
      (node (ref "IC4") (pin "3") (pinfunction "VREFH_3") (pintype "bidirectional"))
      (node (ref "R74") (pin "2") (pinfunction "2_2") (pintype "passive"))
    )
    (net (code "140") (name "VREF_BIAS") (class "Default")
      (node (ref "C51") (pin "1") (pinfunction "1_1") (pintype "passive"))
      (node (ref "IC7") (pin "10") (pinfunction "+IN_10") (pintype "input"))
      (node (ref "IC7") (pin "12") (pinfunction "+IN_12") (pintype "input"))
      (node (ref "IC7") (pin "3") (pinfunction "+IN_3") (pintype "input"))
      (node (ref "IC7") (pin "5") (pinfunction "+IN_5") (pintype "input"))
      (node (ref "R73") (pin "2") (pinfunction "2_2") (pintype "passive"))
      (node (ref "R74") (pin "1") (pinfunction "1_1") (pintype "passive"))
    )
    (net (code "141") (name "X_CLOCK") (class "Default")
      (node (ref "IC2") (pin "41") (pinfunction "PA8/USART1_CK/TIM1_CH1/MCO_41") (pintype "bidirectional"))
      (node (ref "Q3") (pin "C") (pinfunction "C_C") (pintype "passive"))
      (node (ref "R23") (pin "1") (pinfunction "1_1") (pintype "passive"))
    )
    (net (code "142") (name "unconnected-(IC2-PC14{slash}OSC32_IN-Pad3)") (class "Default")
      (node (ref "IC2") (pin "3") (pinfunction "PC14/OSC32_IN_3") (pintype "bidirectional"))
    )
    (net (code "143") (name "unconnected-(J10-2-PadP2)") (class "Default")
      (node (ref "J10") (pin "P2") (pinfunction "2_P2") (pintype "passive"))
    )
    (net (code "144") (name "unconnected-(J11-2-PadP2)") (class "Default")
      (node (ref "J11") (pin "P2") (pinfunction "2_P2") (pintype "passive"))
    )
    (net (code "145") (name "unconnected-(J12-2-PadP2)") (class "Default")
      (node (ref "J12") (pin "P2") (pinfunction "2_P2") (pintype "passive"))
    )
    (net (code "146") (name "unconnected-(J13-2-PadP2)") (class "Default")
      (node (ref "J13") (pin "P2") (pinfunction "2_P2") (pintype "passive"))
    )
    (net (code "147") (name "unconnected-(J14-2-PadP2)") (class "Default")
      (node (ref "J14") (pin "P2") (pinfunction "2_P2") (pintype "passive"))
    )
    (net (code "148") (name "unconnected-(J15-2-PadP2)") (class "Default")
      (node (ref "J15") (pin "P2") (pinfunction "2_P2") (pintype "passive"))
    )
    (net (code "149") (name "unconnected-(J16-2-PadP2)") (class "Default")
      (node (ref "J16") (pin "P2") (pinfunction "2_P2") (pintype "passive"))
    )
    (net (code "150") (name "unconnected-(LED5-RED-Pad3)") (class "Default")
      (node (ref "LED5") (pin "3") (pinfunction "RED_3") (pintype "bidirectional"))
    )
    (net (code "151") (name "unconnected-(SW1A-A1-PadP1)") (class "Default")
      (node (ref "SW1") (pin "P1") (pinfunction "A1_P1") (pintype "passive"))
    )
    (net (code "152") (name "unconnected-(SW1A-B1-PadP4)") (class "Default")
      (node (ref "SW1") (pin "P4") (pinfunction "B1_P4") (pintype "passive"))
    )
    (net (code "153") (name "unconnected-(SW2A-A1-PadP1)") (class "Default")
      (node (ref "SW2") (pin "P1") (pinfunction "A1_P1") (pintype "passive"))
    )
    (net (code "154") (name "unconnected-(SW2A-B1-PadP4)") (class "Default")
      (node (ref "SW2") (pin "P4") (pinfunction "B1_P4") (pintype "passive"))
    )
  )
)
